# hsa_stm32_board.net
KiCad netlist of a schematic drawn in EAGLE
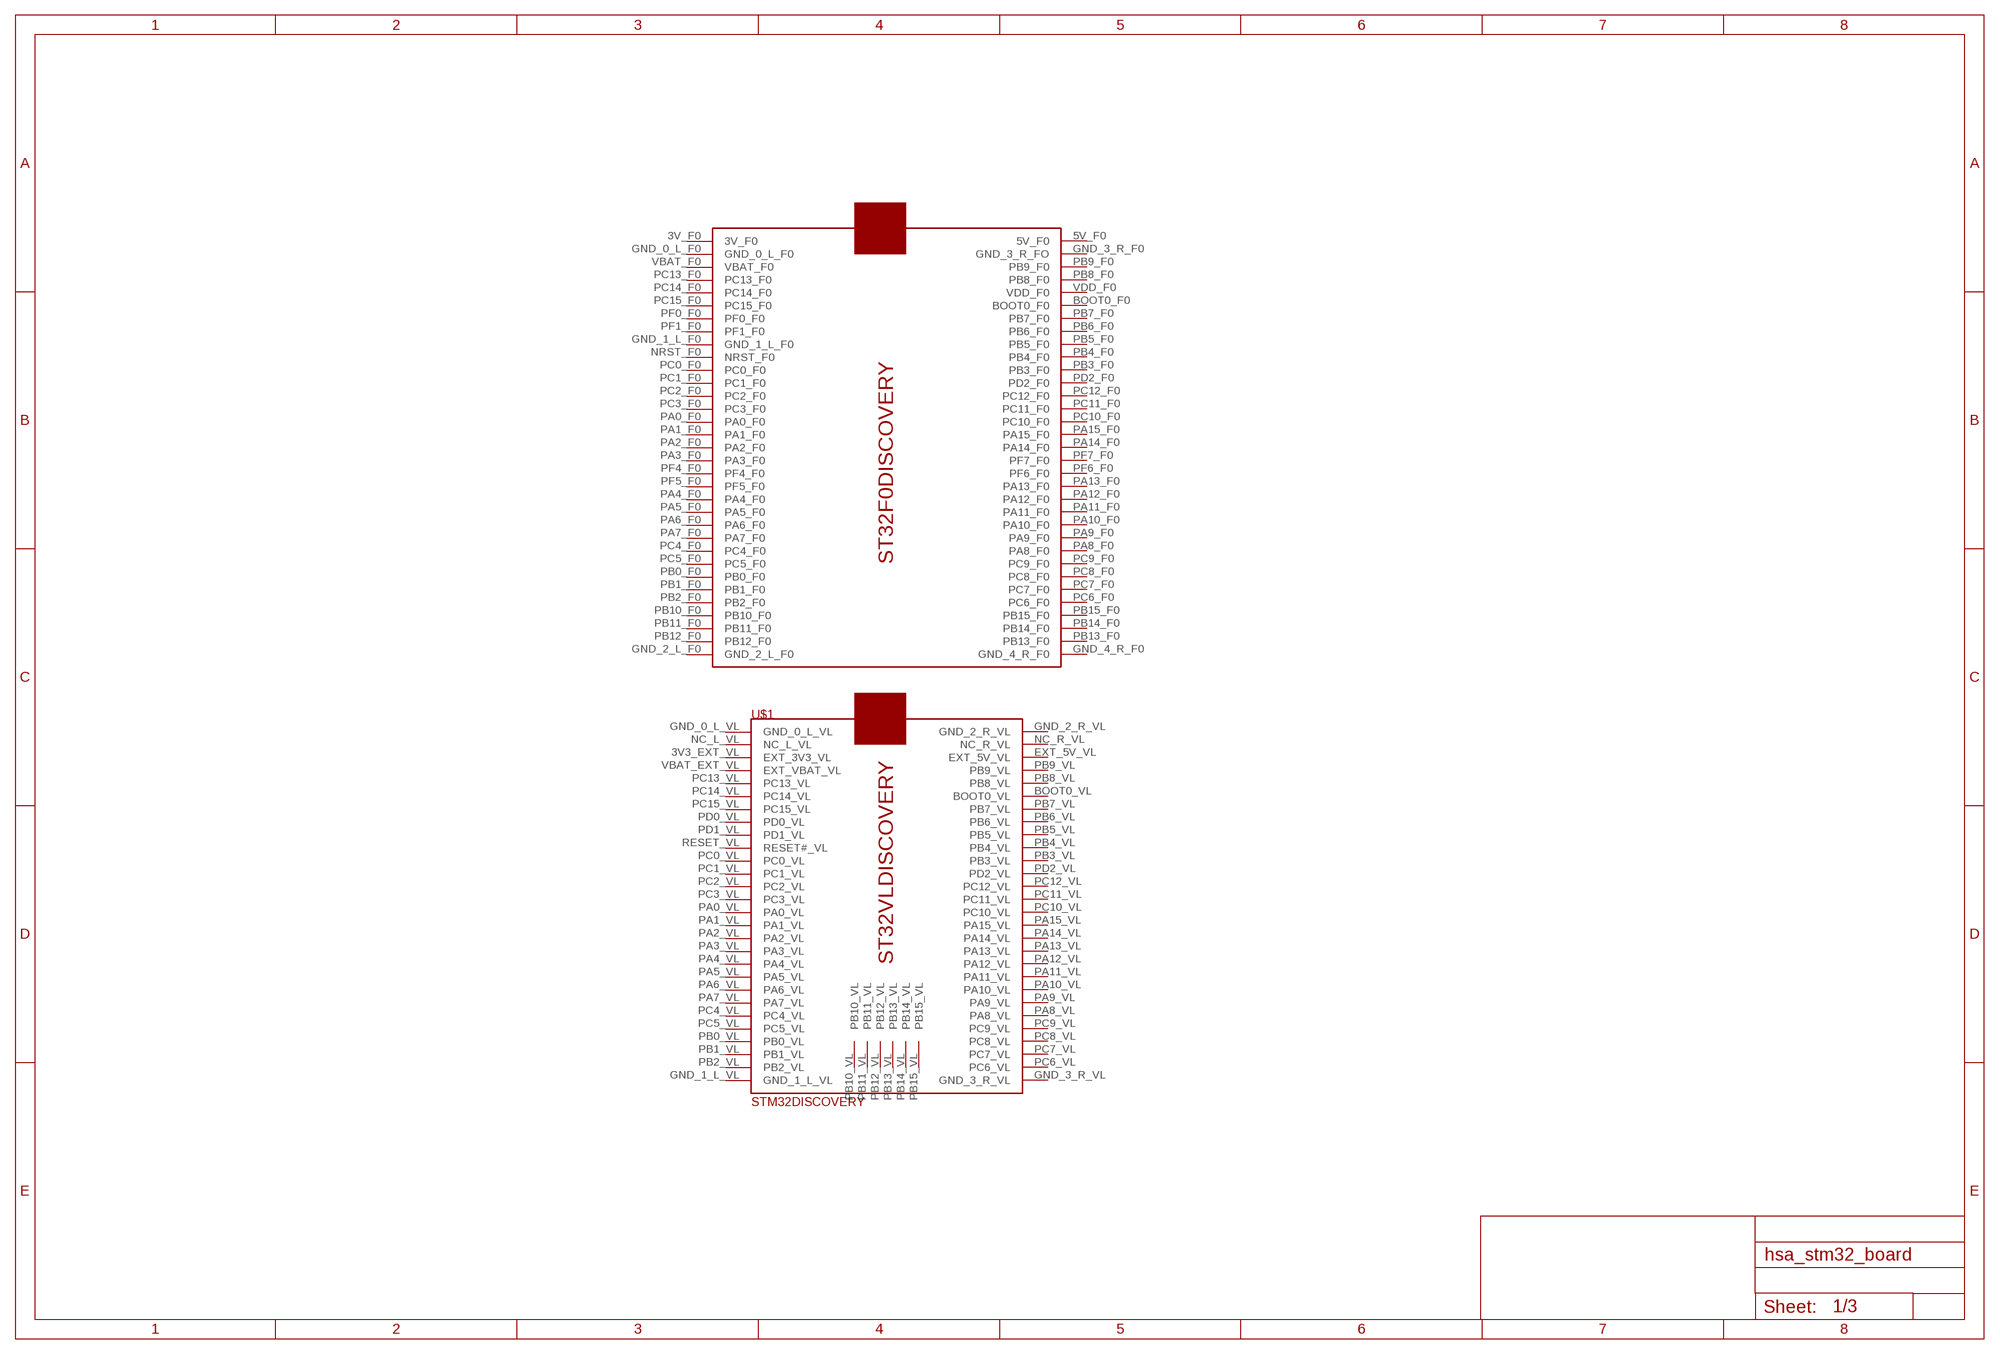
[diagram p0: schematic, sheet 1]
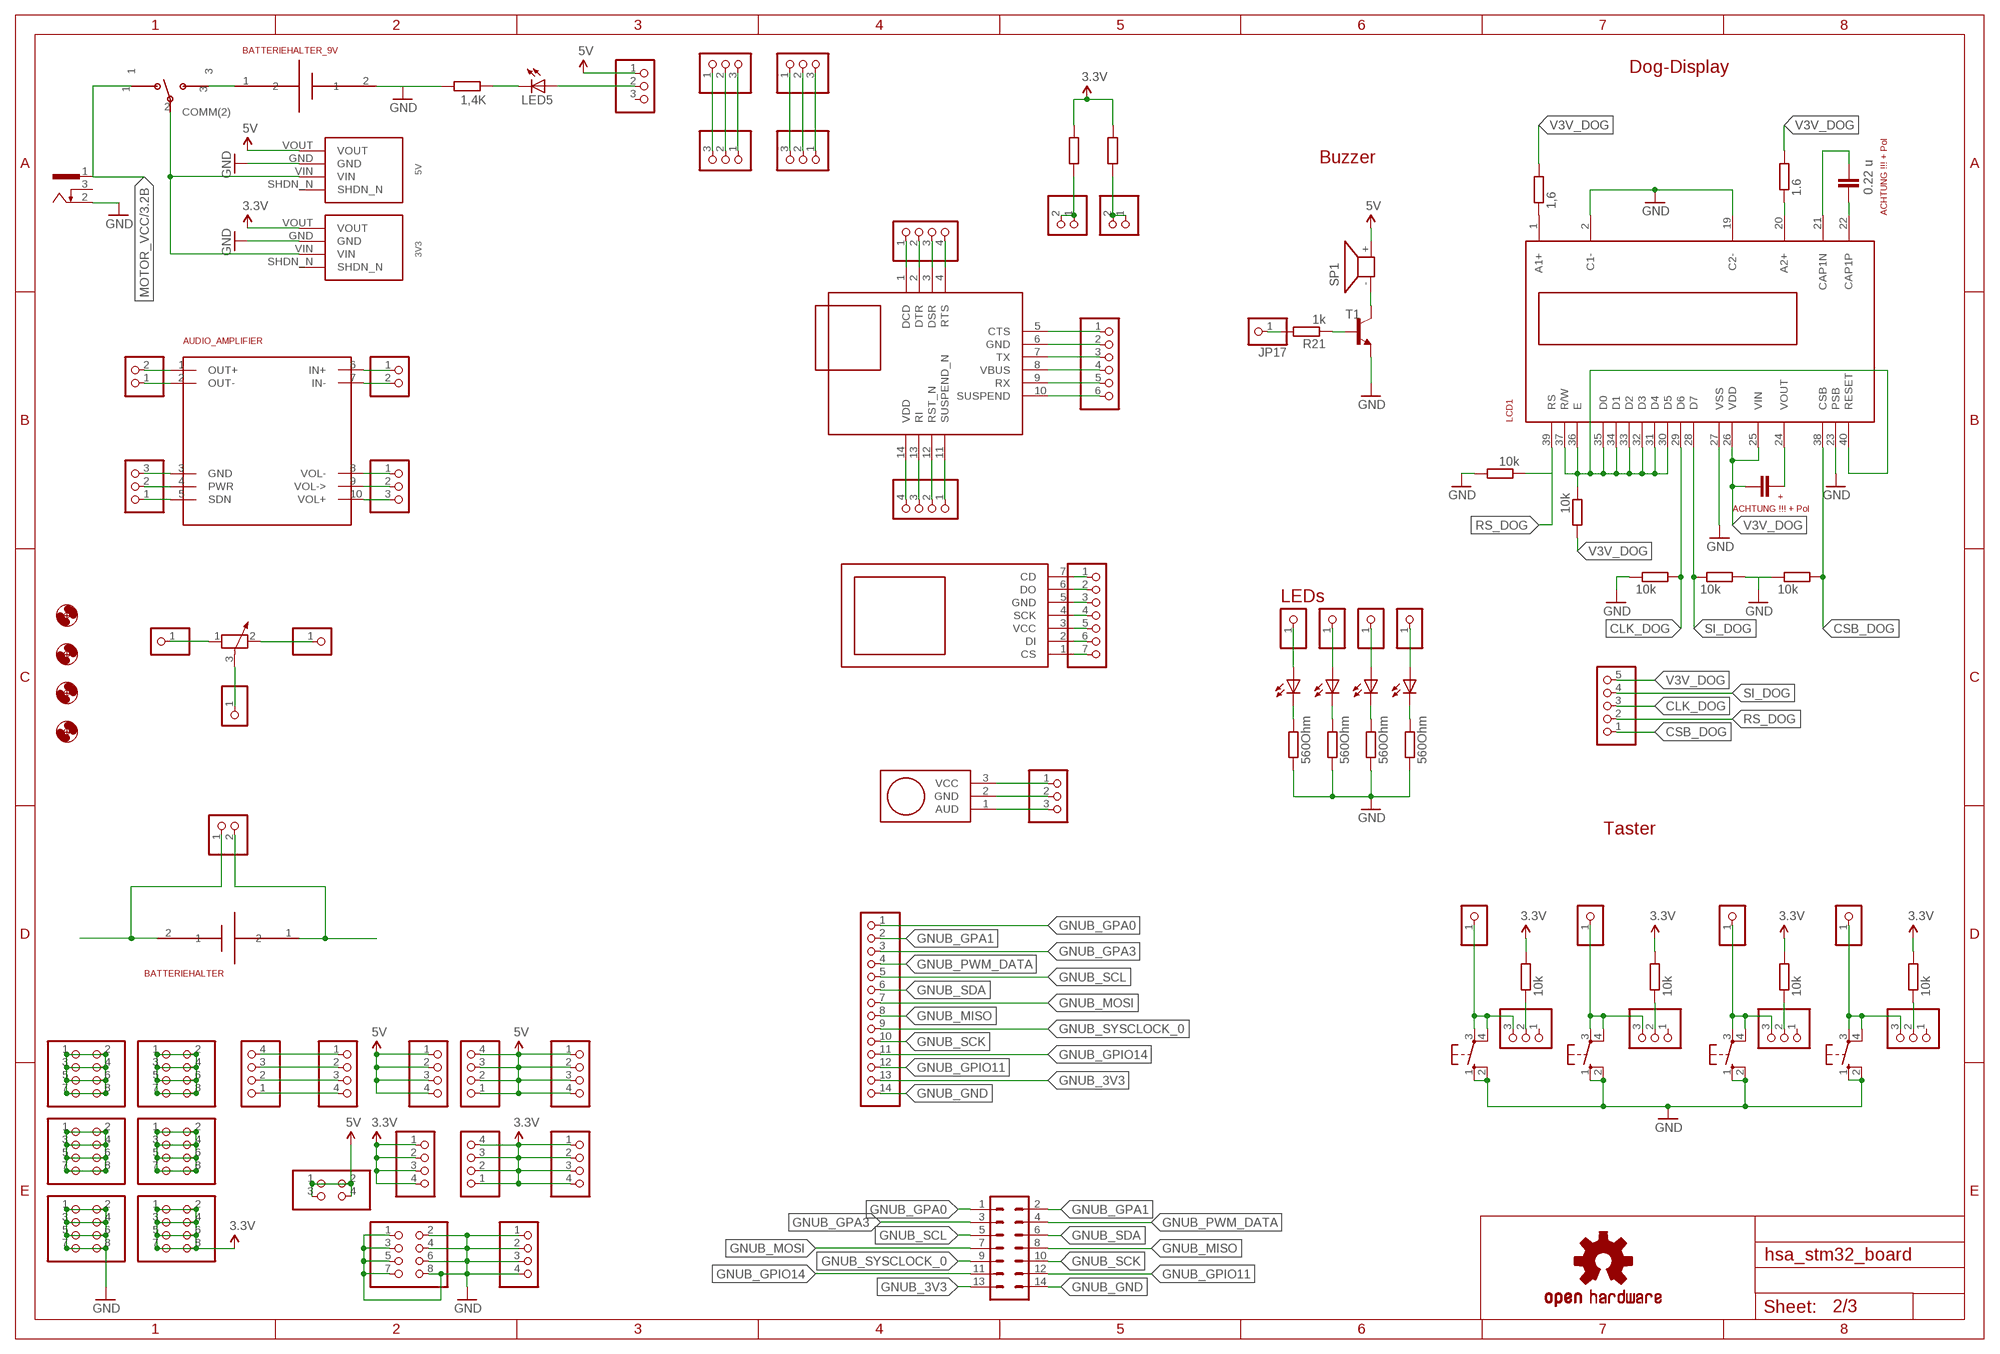
[diagram p1: schematic, sheet 2]
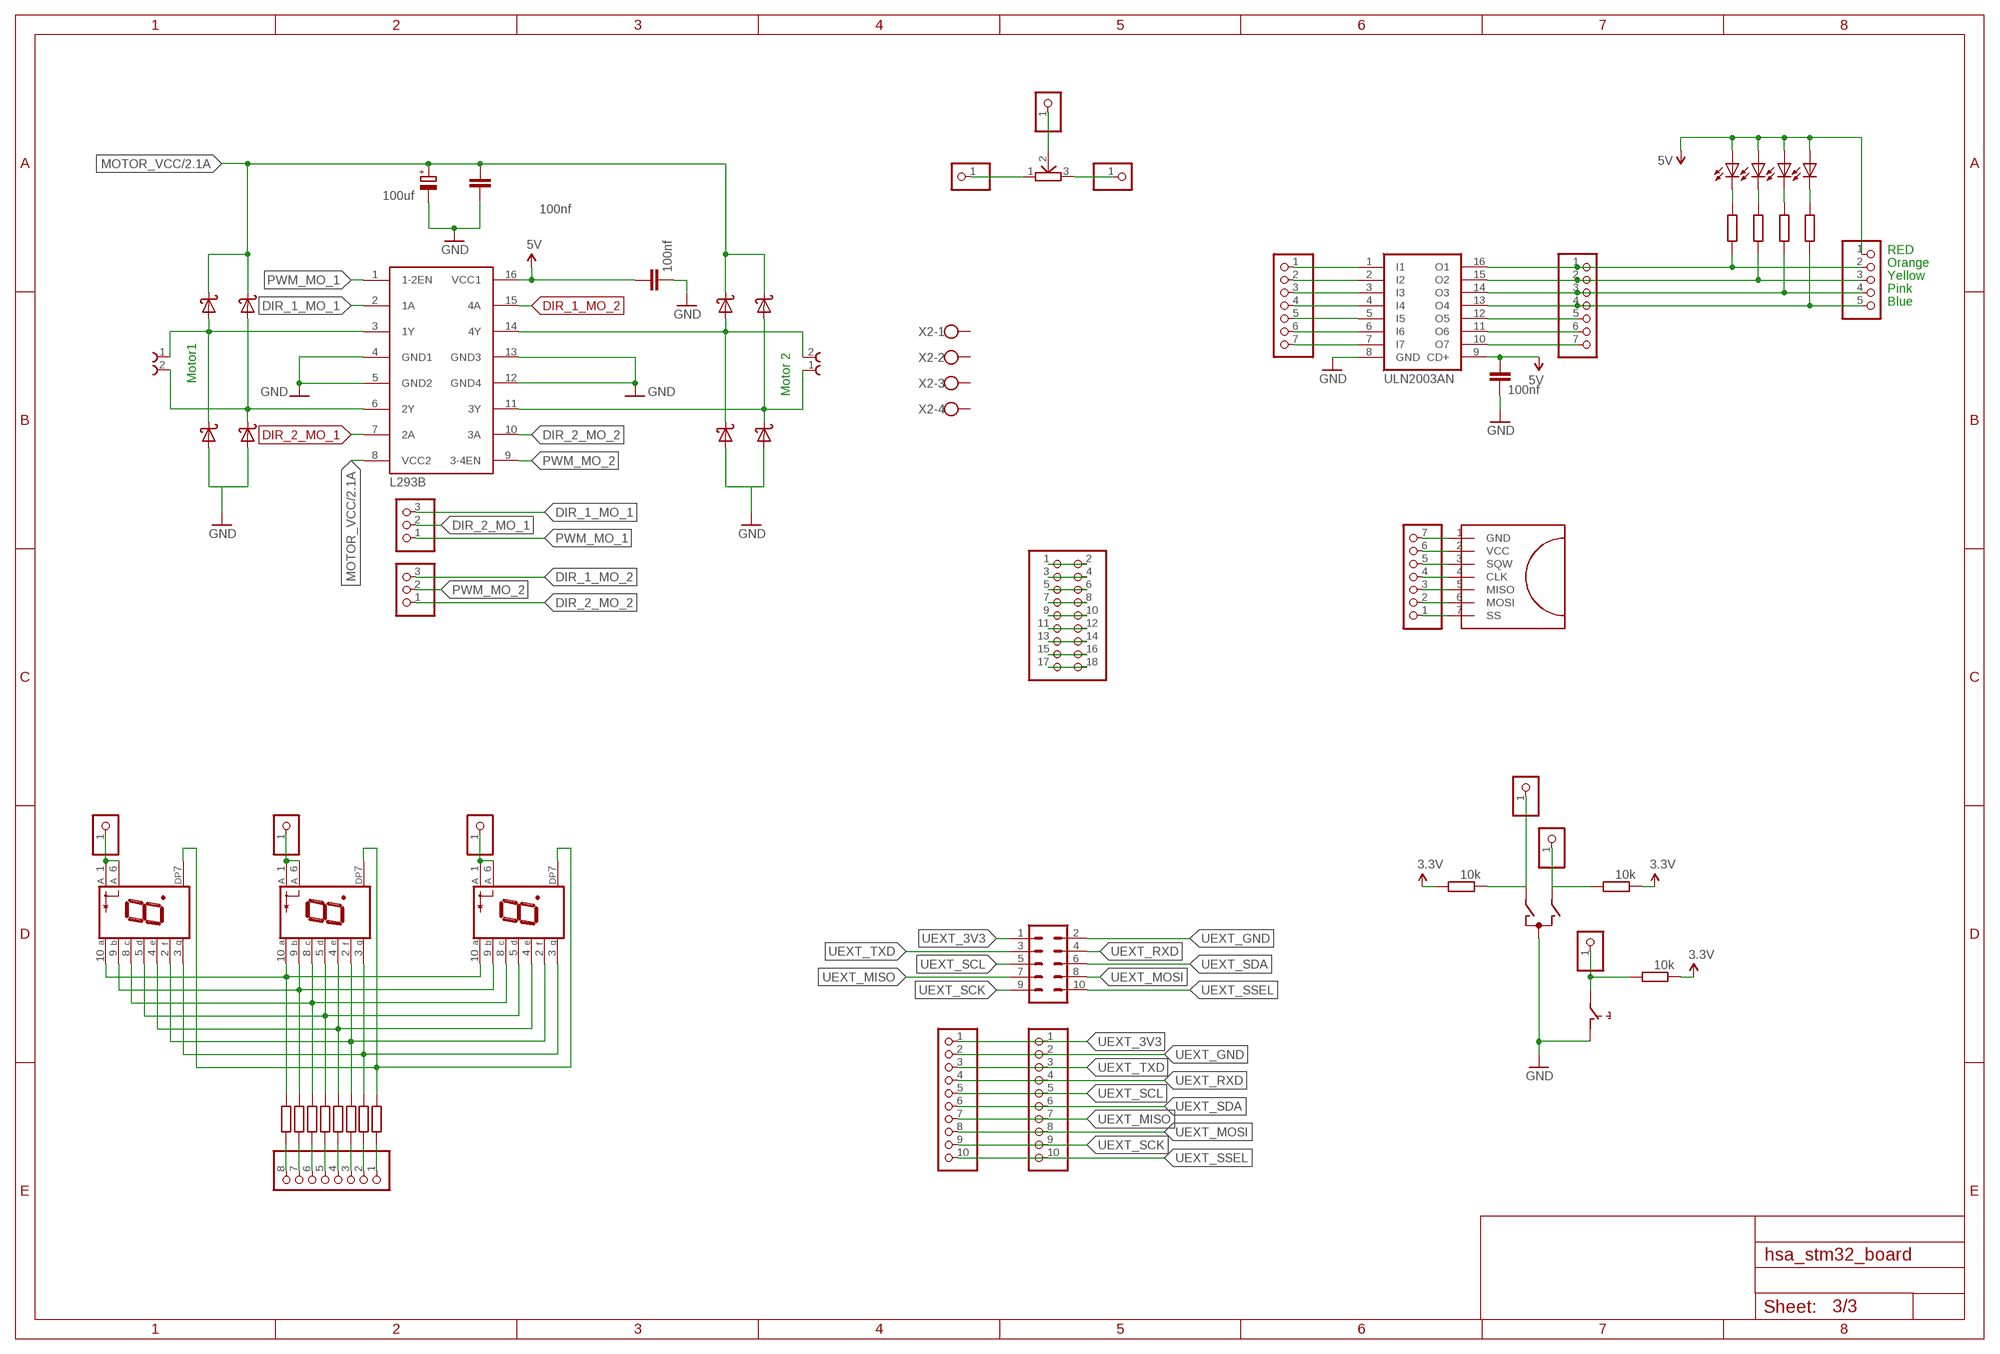
[diagram p2: schematic, sheet 3]

(export (version "E")
  (design (tool "Eeschema 10.0.6"))
  (components
    (comp (ref "C4")
      (value "100nf")
      (footprint "eagle-import:RCL_C025-040X050")
      (libsource (lib "eagle-import") (part "RCL_C-EU025-040X050"))
    )
    (comp (ref "C5")
      (value "100nf")
      (footprint "eagle-import:RCL_C025-040X050")
      (libsource (lib "eagle-import") (part "RCL_C-EU025-040X050"))
    )
    (comp (ref "C6")
      (value "100nf")
      (footprint "eagle-import:RCL_C025-040X050")
      (libsource (lib "eagle-import") (part "RCL_C-EU025-040X050"))
    )
    (comp (ref "C7")
      (value "100uf")
      (footprint "eagle-import:RCL_E2,5-6")
      (libsource (lib "eagle-import") (part "RCL_CPOL-EUE2.5-6"))
    )
    (comp (ref "D1")
      (value "1N5819")
      (footprint "eagle-import:DO41-10")
      (libsource (lib "eagle-import") (part "1N5819"))
    )
    (comp (ref "D2")
      (value "1N5819")
      (footprint "eagle-import:DO41-10")
      (libsource (lib "eagle-import") (part "1N5819"))
    )
    (comp (ref "D3")
      (value "1N5819")
      (footprint "eagle-import:DO41-10")
      (libsource (lib "eagle-import") (part "1N5819"))
    )
    (comp (ref "D4")
      (value "1N5819")
      (footprint "eagle-import:DO41-10")
      (libsource (lib "eagle-import") (part "1N5819"))
    )
    (comp (ref "D5")
      (value "1N5819")
      (footprint "eagle-import:DO41-10")
      (libsource (lib "eagle-import") (part "1N5819"))
    )
    (comp (ref "D6")
      (value "1N5819")
      (footprint "eagle-import:DO41-10")
      (libsource (lib "eagle-import") (part "1N5819"))
    )
    (comp (ref "D7")
      (value "1N5819")
      (footprint "eagle-import:DO41-10")
      (libsource (lib "eagle-import") (part "1N5819"))
    )
    (comp (ref "D8")
      (value "1N5819")
      (footprint "eagle-import:DO41-10")
      (libsource (lib "eagle-import") (part "1N5819"))
    )
    (comp (ref "IC1")
      (value "ULN2003AN")
      (footprint "eagle-import:DIL16")
      (libsource (lib "eagle-import") (part "ULN2003AN"))
    )
    (comp (ref "IC2")
      (value "L293D")
      (footprint "eagle-import:DIL16")
      (libsource (lib "eagle-import") (part "L293D"))
    )
    (comp (ref "JP2")
      (value "PINHD-1X1")
      (footprint "eagle-import:1X01")
      (libsource (lib "eagle-import") (part "PINHD-1X1"))
    )
    (comp (ref "JP3")
      (value "PINHD-1X1")
      (footprint "eagle-import:1X01")
      (libsource (lib "eagle-import") (part "PINHD-1X1"))
    )
    (comp (ref "JP13")
      (value "PINHD-1X1")
      (footprint "eagle-import:1X01")
      (libsource (lib "eagle-import") (part "PINHD-1X1"))
    )
    (comp (ref "JP20")
      (value "PINHD-1X10")
      (footprint "eagle-import:1X10")
      (libsource (lib "eagle-import") (part "PINHD-1X10"))
    )
    (comp (ref "JP21")
      (value "PINHD-1X7")
      (footprint "eagle-import:1X07")
      (libsource (lib "eagle-import") (part "PINHD-1X7"))
    )
    (comp (ref "JP22")
      (value "PINHD-1X8")
      (footprint "eagle-import:1X08")
      (libsource (lib "eagle-import") (part "PINHD-1X8"))
    )
    (comp (ref "JP23")
      (value "PINHD-1X1")
      (footprint "eagle-import:1X01")
      (libsource (lib "eagle-import") (part "PINHD-1X1"))
    )
    (comp (ref "JP25")
      (value "PINHD-1X5/90")
      (footprint "eagle-import:1X05_90")
      (libsource (lib "eagle-import") (part "PINHD-1X5/90"))
    )
    (comp (ref "JP26")
      (value "PINHD-1X7")
      (footprint "eagle-import:1X07")
      (libsource (lib "eagle-import") (part "PINHD-1X7"))
    )
    (comp (ref "JP35")
      (value "PINHD-1X7")
      (footprint "eagle-import:1X07")
      (libsource (lib "eagle-import") (part "PINHD-1X7"))
    )
    (comp (ref "JP53")
      (value "PINHD-1X1")
      (footprint "eagle-import:1X01")
      (libsource (lib "eagle-import") (part "PINHD-1X1"))
    )
    (comp (ref "JP54")
      (value "PINHD-1X1")
      (footprint "eagle-import:1X01")
      (libsource (lib "eagle-import") (part "PINHD-1X1"))
    )
    (comp (ref "JP55")
      (value "PINHD-1X1")
      (footprint "eagle-import:1X01")
      (libsource (lib "eagle-import") (part "PINHD-1X1"))
    )
    (comp (ref "JP56")
      (value "PINHD-2X9")
      (footprint "eagle-import:2X09")
      (libsource (lib "eagle-import") (part "PINHD-2X9"))
    )
    (comp (ref "JP57")
      (value "PINHD-1X3")
      (footprint "eagle-import:1X03")
      (libsource (lib "eagle-import") (part "PINHD-1X3"))
    )
    (comp (ref "JP58")
      (value "PINHD-1X3")
      (footprint "eagle-import:1X03")
      (libsource (lib "eagle-import") (part "PINHD-1X3"))
    )
    (comp (ref "JP63")
      (value "PINHD-1X10")
      (footprint "eagle-import:1X10")
      (libsource (lib "eagle-import") (part "PINHD-1X10"))
    )
    (comp (ref "JP72")
      (value "PINHD-1X1")
      (footprint "eagle-import:1X01")
      (libsource (lib "eagle-import") (part "PINHD-1X1"))
    )
    (comp (ref "JP73")
      (value "PINHD-1X1")
      (footprint "eagle-import:1X01")
      (libsource (lib "eagle-import") (part "PINHD-1X1"))
    )
    (comp (ref "K1")
      (value "691210910002")
      (footprint "eagle-import:691210910002")
      (libsource (lib "eagle-import") (part "691210910002"))
    )
    (comp (ref "K2")
      (value "691210910002")
      (footprint "eagle-import:691210910002")
      (libsource (lib "eagle-import") (part "691210910002"))
    )
    (comp (ref "LED6")
      (value "LA-401MD")
      (footprint "eagle-import:LA-401")
      (libsource (lib "eagle-import") (part "LA-401DM"))
    )
    (comp (ref "LED7")
      (value "LA-401MD")
      (footprint "eagle-import:LA-401")
      (libsource (lib "eagle-import") (part "LA-401DM"))
    )
    (comp (ref "LED8")
      (value "LA-401MD")
      (footprint "eagle-import:LA-401")
      (libsource (lib "eagle-import") (part "LA-401DM"))
    )
    (comp (ref "LED9")
      (value "LED3MM")
      (footprint "eagle-import:LED3MM")
      (libsource (lib "eagle-import") (part "LED3MM"))
    )
    (comp (ref "LED10")
      (value "LED3MM")
      (footprint "eagle-import:LED3MM")
      (libsource (lib "eagle-import") (part "LED3MM"))
    )
    (comp (ref "LED11")
      (value "LED3MM")
      (footprint "eagle-import:LED3MM")
      (libsource (lib "eagle-import") (part "LED3MM"))
    )
    (comp (ref "LED12")
      (value "LED3MM")
      (footprint "eagle-import:LED3MM")
      (libsource (lib "eagle-import") (part "LED3MM"))
    )
    (comp (ref "R18")
      (value "10k")
      (footprint "eagle-import:0207_10")
      (libsource (lib "eagle-import") (part "R-EU_0207/10"))
    )
    (comp (ref "R19")
      (value "10k")
      (footprint "eagle-import:0207_10")
      (libsource (lib "eagle-import") (part "R-EU_0207/10"))
    )
    (comp (ref "R20")
      (value "10k")
      (footprint "eagle-import:0207_10")
      (libsource (lib "eagle-import") (part "R-EU_0207/10"))
    )
    (comp (ref "R24")
      (value "R-EU_0207/10")
      (footprint "eagle-import:0207_10")
      (libsource (lib "eagle-import") (part "R-EU_0207/10"))
    )
    (comp (ref "R25")
      (value "R-EU_0207/10")
      (footprint "eagle-import:0207_10")
      (libsource (lib "eagle-import") (part "R-EU_0207/10"))
    )
    (comp (ref "R26")
      (value "R-EU_0207/10")
      (footprint "eagle-import:0207_10")
      (libsource (lib "eagle-import") (part "R-EU_0207/10"))
    )
    (comp (ref "R27")
      (value "R-EU_0207/10")
      (footprint "eagle-import:0207_10")
      (libsource (lib "eagle-import") (part "R-EU_0207/10"))
    )
    (comp (ref "R28")
      (value "R-EU_0207/10")
      (footprint "eagle-import:0207_10")
      (libsource (lib "eagle-import") (part "R-EU_0207/10"))
    )
    (comp (ref "R29")
      (value "R-EU_0207/10")
      (footprint "eagle-import:0207_10")
      (libsource (lib "eagle-import") (part "R-EU_0207/10"))
    )
    (comp (ref "R30")
      (value "R-EU_0207/10")
      (footprint "eagle-import:0207_10")
      (libsource (lib "eagle-import") (part "R-EU_0207/10"))
    )
    (comp (ref "R31")
      (value "R-EU_0207/10")
      (footprint "eagle-import:0207_10")
      (libsource (lib "eagle-import") (part "R-EU_0207/10"))
    )
    (comp (ref "R32")
      (value "R-EU_0207/10")
      (footprint "eagle-import:0207_10")
      (libsource (lib "eagle-import") (part "R-EU_0207/10"))
    )
    (comp (ref "R33")
      (value "R-EU_0207/10")
      (footprint "eagle-import:0207_10")
      (libsource (lib "eagle-import") (part "R-EU_0207/10"))
    )
    (comp (ref "R34")
      (value "R-EU_0207/10")
      (footprint "eagle-import:0207_10")
      (libsource (lib "eagle-import") (part "R-EU_0207/10"))
    )
    (comp (ref "R35")
      (value "R-EU_0207/10")
      (footprint "eagle-import:0207_10")
      (libsource (lib "eagle-import") (part "R-EU_0207/10"))
    )
    (comp (ref "SV2")
      (value "CON-HARTING-ML_ML10")
      (footprint "eagle-import:CON-HARTING-ML_ML10")
      (libsource (lib "eagle-import") (part "CON-HARTING-ML_ML10"))
    )
    (comp (ref "SW1")
      (value "EC12E_SW")
      (footprint "eagle-import:ALPS_EC12E_SW")
      (fields (field (name "MPN") "EC12E2424407"))
      (libsource (lib "eagle-import") (part "EC12E_SW"))
    )
    (comp (ref "U$10")
      (value "RTC")
      (footprint "eagle-import:RTC")
      (libsource (lib "eagle-import") (part "RTC"))
    )
    (comp (ref "U$17")
      (value "THUMBWHEEL_POTI")
      (footprint "eagle-import:THUMBWHEEL_POTI")
      (libsource (lib "eagle-import") (part "THUMBWHEEL_POTI"))
    )
    (comp (ref "X2")
      (value "W237-4")
      (footprint "eagle-import:W237-4")
      (libsource (lib "eagle-import") (part "W237-4"))
    )
    (comp (ref "U$1")
      (value "STM32DISCOVERY")
      (footprint "eagle-import:STM32DISCOVERY")
      (libsource (lib "eagle-import") (part "STM32DISCOVERY"))
    )
    (comp (ref "3V3")
      (value "VOLTAGE_REGULATOR")
      (footprint "eagle-import:VOL_REG")
      (libsource (lib "eagle-import") (part "VOLTAGE_REGULATOR"))
    )
    (comp (ref "5V")
      (value "VOLTAGE_REGULATOR")
      (footprint "eagle-import:VOL_REG")
      (libsource (lib "eagle-import") (part "VOLTAGE_REGULATOR"))
    )
    (comp (ref "C2")
      (value "0.22 u")
      (footprint "eagle-import:C025-040X050")
      (libsource (lib "eagle-import") (part "C-EU025-040X050"))
    )
    (comp (ref "C3")
      (value "1 u")
      (footprint "eagle-import:C025-040X050")
      (libsource (lib "eagle-import") (part "C-EU025-040X050"))
    )
    (comp (ref "H1")
      (value "MOUNT-HOLE6.0")
      (footprint "eagle-import:6,0")
      (libsource (lib "eagle-import") (part "MOUNT-HOLE6.0"))
    )
    (comp (ref "H2")
      (value "MOUNT-HOLE6.0")
      (footprint "eagle-import:6,0")
      (libsource (lib "eagle-import") (part "MOUNT-HOLE6.0"))
    )
    (comp (ref "H3")
      (value "MOUNT-HOLE6.0")
      (footprint "eagle-import:6,0")
      (libsource (lib "eagle-import") (part "MOUNT-HOLE6.0"))
    )
    (comp (ref "H4")
      (value "MOUNT-HOLE6.0")
      (footprint "eagle-import:6,0")
      (libsource (lib "eagle-import") (part "MOUNT-HOLE6.0"))
    )
    (comp (ref "JP1")
      (value "PINHD-1X5")
      (footprint "eagle-import:1X05")
      (libsource (lib "eagle-import") (part "PINHD-1X5"))
    )
    (comp (ref "JP4")
      (value "PINHD-1X3")
      (footprint "eagle-import:1X03")
      (libsource (lib "eagle-import") (part "PINHD-1X3"))
    )
    (comp (ref "JP5")
      (value "PINHD-1X1")
      (footprint "eagle-import:1X01")
      (libsource (lib "eagle-import") (part "PINHD-1X1"))
    )
    (comp (ref "JP6")
      (value "PINHD-1X1")
      (footprint "eagle-import:1X01")
      (libsource (lib "eagle-import") (part "PINHD-1X1"))
    )
    (comp (ref "JP7")
      (value "PINHD-1X1")
      (footprint "eagle-import:1X01")
      (libsource (lib "eagle-import") (part "PINHD-1X1"))
    )
    (comp (ref "JP8")
      (value "PINHD-1X1")
      (footprint "eagle-import:1X01")
      (libsource (lib "eagle-import") (part "PINHD-1X1"))
    )
    (comp (ref "JP9")
      (value "PINHD-1X1")
      (footprint "eagle-import:1X01")
      (libsource (lib "eagle-import") (part "PINHD-1X1"))
    )
    (comp (ref "JP10")
      (value "PINHD-1X1")
      (footprint "eagle-import:1X01")
      (libsource (lib "eagle-import") (part "PINHD-1X1"))
    )
    (comp (ref "JP11")
      (value "PINHD-1X1")
      (footprint "eagle-import:1X01")
      (libsource (lib "eagle-import") (part "PINHD-1X1"))
    )
    (comp (ref "JP12")
      (value "PINHD-1X1")
      (footprint "eagle-import:1X01")
      (libsource (lib "eagle-import") (part "PINHD-1X1"))
    )
    (comp (ref "JP14")
      (value "PINHD-1X1")
      (footprint "eagle-import:1X01")
      (libsource (lib "eagle-import") (part "PINHD-1X1"))
    )
    (comp (ref "JP15")
      (value "PINHD-1X1")
      (footprint "eagle-import:1X01")
      (libsource (lib "eagle-import") (part "PINHD-1X1"))
    )
    (comp (ref "JP16")
      (value "PINHD-1X1")
      (footprint "eagle-import:1X01")
      (libsource (lib "eagle-import") (part "PINHD-1X1"))
    )
    (comp (ref "JP17")
      (value "PINHD-1X1")
      (footprint "eagle-import:1X01")
      (libsource (lib "eagle-import") (part "PINHD-1X1"))
    )
    (comp (ref "JP18")
      (value "PINHD-2X4")
      (footprint "eagle-import:2X04")
      (libsource (lib "eagle-import") (part "PINHD-2X4"))
    )
    (comp (ref "JP24")
      (value "PINHD-1X4")
      (footprint "eagle-import:1X04")
      (libsource (lib "eagle-import") (part "PINHD-1X4"))
    )
    (comp (ref "JP27")
      (value "PINHD-1X4/90")
      (footprint "eagle-import:1X04_90")
      (libsource (lib "eagle-import") (part "PINHD-1X4/90"))
    )
    (comp (ref "JP28")
      (value "PINHD-1X4")
      (footprint "eagle-import:1X04")
      (libsource (lib "eagle-import") (part "PINHD-1X4"))
    )
    (comp (ref "JP29")
      (value "PINHD-1X4")
      (footprint "eagle-import:1X04")
      (libsource (lib "eagle-import") (part "PINHD-1X4"))
    )
    (comp (ref "JP30")
      (value "PINHD-1X3")
      (footprint "eagle-import:1X03")
      (libsource (lib "eagle-import") (part "PINHD-1X3"))
    )
    (comp (ref "JP31")
      (value "PINHD-1X2")
      (footprint "eagle-import:1X02")
      (libsource (lib "eagle-import") (part "PINHD-1X2"))
    )
    (comp (ref "JP32")
      (value "PINHD-1X2")
      (footprint "eagle-import:1X02")
      (libsource (lib "eagle-import") (part "PINHD-1X2"))
    )
    (comp (ref "JP33")
      (value "PINHD-1X3")
      (footprint "eagle-import:1X03")
      (libsource (lib "eagle-import") (part "PINHD-1X3"))
    )
    (comp (ref "JP34")
      (value "PINHD-1X3")
      (footprint "eagle-import:1X03")
      (libsource (lib "eagle-import") (part "PINHD-1X3"))
    )
    (comp (ref "JP36")
      (value "PINHD-1X4")
      (footprint "eagle-import:1X04")
      (libsource (lib "eagle-import") (part "PINHD-1X4"))
    )
    (comp (ref "JP37")
      (value "PINHD-1X4")
      (footprint "eagle-import:1X04")
      (libsource (lib "eagle-import") (part "PINHD-1X4"))
    )
    (comp (ref "JP38")
      (value "PINHD-1X6")
      (footprint "eagle-import:1X06")
      (libsource (lib "eagle-import") (part "PINHD-1X6"))
    )
    (comp (ref "JP39")
      (value "PINHD-1X7")
      (footprint "eagle-import:1X07")
      (libsource (lib "eagle-import") (part "PINHD-1X7"))
    )
    (comp (ref "JP40")
      (value "PINHD-1X4")
      (footprint "eagle-import:1X04")
      (libsource (lib "eagle-import") (part "PINHD-1X4"))
    )
    (comp (ref "JP41")
      (value "PINHD-1X4")
      (footprint "eagle-import:1X04")
      (libsource (lib "eagle-import") (part "PINHD-1X4"))
    )
    (comp (ref "JP42")
      (value "PINHD-1X4")
      (footprint "eagle-import:1X04")
      (libsource (lib "eagle-import") (part "PINHD-1X4"))
    )
    (comp (ref "JP43")
      (value "PINHD-1X2")
      (footprint "eagle-import:1X02")
      (libsource (lib "eagle-import") (part "PINHD-1X2"))
    )
    (comp (ref "JP44")
      (value "PINHD-2X4")
      (footprint "eagle-import:2X04")
      (libsource (lib "eagle-import") (part "PINHD-2X4"))
    )
    (comp (ref "JP45")
      (value "PINHD-2X4")
      (footprint "eagle-import:2X04")
      (libsource (lib "eagle-import") (part "PINHD-2X4"))
    )
    (comp (ref "JP47")
      (value "PINHD-1X4")
      (footprint "eagle-import:1X04")
      (libsource (lib "eagle-import") (part "PINHD-1X4"))
    )
    (comp (ref "JP48")
      (value "PINHD-1X4")
      (footprint "eagle-import:1X04")
      (libsource (lib "eagle-import") (part "PINHD-1X4"))
    )
    (comp (ref "JP49")
      (value "PINHD-1X3/90")
      (footprint "eagle-import:1X03_90")
      (libsource (lib "eagle-import") (part "PINHD-1X3/90"))
    )
    (comp (ref "JP50")
      (value "PINHD-1X3")
      (footprint "eagle-import:1X03")
      (libsource (lib "eagle-import") (part "PINHD-1X3"))
    )
    (comp (ref "JP51")
      (value "PINHD-1X3/90")
      (footprint "eagle-import:1X03_90")
      (libsource (lib "eagle-import") (part "PINHD-1X3/90"))
    )
    (comp (ref "JP52")
      (value "PINHD-1X3")
      (footprint "eagle-import:1X03")
      (libsource (lib "eagle-import") (part "PINHD-1X3"))
    )
    (comp (ref "JP59")
      (value "PINHD-1X3")
      (footprint "eagle-import:1X03")
      (libsource (lib "eagle-import") (part "PINHD-1X3"))
    )
    (comp (ref "JP60")
      (value "PINHD-1X3")
      (footprint "eagle-import:1X03")
      (libsource (lib "eagle-import") (part "PINHD-1X3"))
    )
    (comp (ref "JP61")
      (value "PINHD-1X3")
      (footprint "eagle-import:1X03")
      (libsource (lib "eagle-import") (part "PINHD-1X3"))
    )
    (comp (ref "JP62")
      (value "PINHD-1X3")
      (footprint "eagle-import:1X03")
      (libsource (lib "eagle-import") (part "PINHD-1X3"))
    )
    (comp (ref "JP64")
      (value "PINHD-1X14")
      (footprint "eagle-import:1X14")
      (libsource (lib "eagle-import") (part "PINHD-1X14"))
    )
    (comp (ref "JP65")
      (value "PINHD-1X2")
      (footprint "eagle-import:1X02")
      (libsource (lib "eagle-import") (part "PINHD-1X2"))
    )
    (comp (ref "JP66")
      (value "PINHD-1X2")
      (footprint "eagle-import:1X02")
      (libsource (lib "eagle-import") (part "PINHD-1X2"))
    )
    (comp (ref "JP67")
      (value "PINHD-2X4")
      (footprint "eagle-import:2X04")
      (libsource (lib "eagle-import") (part "PINHD-2X4"))
    )
    (comp (ref "JP68")
      (value "PINHD-2X4")
      (footprint "eagle-import:2X04")
      (libsource (lib "eagle-import") (part "PINHD-2X4"))
    )
    (comp (ref "JP69")
      (value "PINHD-2X4")
      (footprint "eagle-import:2X04")
      (libsource (lib "eagle-import") (part "PINHD-2X4"))
    )
    (comp (ref "JP70")
      (value "PINHD-2X4")
      (footprint "eagle-import:2X04")
      (libsource (lib "eagle-import") (part "PINHD-2X4"))
    )
    (comp (ref "JP71")
      (value "PINHD-2X2")
      (footprint "eagle-import:2X02")
      (libsource (lib "eagle-import") (part "PINHD-2X2"))
    )
    (comp (ref "LCD1")
      (value "ZEITERFASSUNG_-OPTO_DOGM")
      (footprint "eagle-import:ZEITERFASSUNG_-OPTO_DOGM")
      (libsource (lib "eagle-import") (part "ZEITERFASSUNG_-OPTO_DOGM"))
    )
    (comp (ref "LED1")
      (value "LED5MM")
      (footprint "eagle-import:LED5MM")
      (libsource (lib "eagle-import") (part "LED5MM"))
    )
    (comp (ref "LED2")
      (value "LED5MM")
      (footprint "eagle-import:LED5MM")
      (libsource (lib "eagle-import") (part "LED5MM"))
    )
    (comp (ref "LED3")
      (value "LED5MM")
      (footprint "eagle-import:LED5MM")
      (libsource (lib "eagle-import") (part "LED5MM"))
    )
    (comp (ref "LED4")
      (value "LED5MM")
      (footprint "eagle-import:LED5MM")
      (libsource (lib "eagle-import") (part "LED5MM"))
    )
    (comp (ref "LED5")
      (value "LED5MM")
      (footprint "eagle-import:LED5MM")
      (libsource (lib "eagle-import") (part "LED5MM"))
    )
    (comp (ref "LOGO1")
      (value "OSHW-LOGOL")
      (footprint "eagle-import:OSHW-LOGO-L")
      (libsource (lib "eagle-import") (part "OSHW-LOGOL"))
    )
    (comp (ref "R1")
      (value "560Ohm")
      (footprint "eagle-import:0207_10")
      (libsource (lib "eagle-import") (part "R-EU_0207/10"))
    )
    (comp (ref "R2")
      (value "560Ohm")
      (footprint "eagle-import:0207_10")
      (libsource (lib "eagle-import") (part "R-EU_0207/10"))
    )
    (comp (ref "R3")
      (value "560Ohm")
      (footprint "eagle-import:0207_10")
      (libsource (lib "eagle-import") (part "R-EU_0207/10"))
    )
    (comp (ref "R4")
      (value "560Ohm")
      (footprint "eagle-import:0207_10")
      (libsource (lib "eagle-import") (part "R-EU_0207/10"))
    )
    (comp (ref "R5")
      (value "RCL_POTENTIOMETER_PT-10")
      (footprint "eagle-import:RCL_PT-10")
      (libsource (lib "eagle-import") (part "RCL_POTENTIOMETER_PT-10"))
    )
    (comp (ref "R6")
      (value "1,4K")
      (footprint "eagle-import:0207_10")
      (libsource (lib "eagle-import") (part "R-EU_0207/10"))
    )
    (comp (ref "R7")
      (value "1.6")
      (footprint "eagle-import:0207_10")
      (libsource (lib "eagle-import") (part "R-EU_0207/10"))
    )
    (comp (ref "R8")
      (value "1,6")
      (footprint "eagle-import:0207_10")
      (libsource (lib "eagle-import") (part "R-EU_0207/10"))
    )
    (comp (ref "R9")
      (value "10k")
      (footprint "eagle-import:0207_10")
      (libsource (lib "eagle-import") (part "R-EU_0207/10"))
    )
    (comp (ref "R10")
      (value "10k")
      (footprint "eagle-import:0207_10")
      (libsource (lib "eagle-import") (part "R-EU_0207/10"))
    )
    (comp (ref "R11")
      (value "10k")
      (footprint "eagle-import:0207_10")
      (libsource (lib "eagle-import") (part "R-EU_0207/10"))
    )
    (comp (ref "R12")
      (value "10k")
      (footprint "eagle-import:0207_10")
      (libsource (lib "eagle-import") (part "R-EU_0207/10"))
    )
    (comp (ref "R13")
      (value "10k")
      (footprint "eagle-import:0207_10")
      (libsource (lib "eagle-import") (part "R-EU_0207/10"))
    )
    (comp (ref "R14")
      (value "10k")
      (footprint "eagle-import:0207_10")
      (libsource (lib "eagle-import") (part "R-EU_0207/10"))
    )
    (comp (ref "R15")
      (value "10k")
      (footprint "eagle-import:0207_10")
      (libsource (lib "eagle-import") (part "R-EU_0207/10"))
    )
    (comp (ref "R16")
      (value "10k")
      (footprint "eagle-import:0207_10")
      (libsource (lib "eagle-import") (part "R-EU_0207/10"))
    )
    (comp (ref "R17")
      (value "10k")
      (footprint "eagle-import:0207_10")
      (libsource (lib "eagle-import") (part "R-EU_0207/10"))
    )
    (comp (ref "R21")
      (value "1k")
      (footprint "eagle-import:0207_10")
      (libsource (lib "eagle-import") (part "R-EU_0207/10"))
    )
    (comp (ref "R22")
      (value "R-EU_0207/10")
      (footprint "eagle-import:0207_10")
      (libsource (lib "eagle-import") (part "R-EU_0207/10"))
    )
    (comp (ref "R23")
      (value "R-EU_0207/10")
      (footprint "eagle-import:0207_10")
      (libsource (lib "eagle-import") (part "R-EU_0207/10"))
    )
    (comp (ref "S1")
      (value "CPU-K_MODULE_REV3.0_SWITCH-OMRON_10-XX")
      (footprint "eagle-import:CPU-K_MODULE_REV3.0_SWITCH-OMRON_B3F-10XX")
      (libsource (lib "eagle-import") (part "CPU-K_MODULE_REV3.0_SWITCH-OMRON_10-XX"))
    )
    (comp (ref "S2")
      (value "CPU-K_MODULE_REV3.0_SWITCH-OMRON_10-XX")
      (footprint "eagle-import:CPU-K_MODULE_REV3.0_SWITCH-OMRON_B3F-10XX")
      (libsource (lib "eagle-import") (part "CPU-K_MODULE_REV3.0_SWITCH-OMRON_10-XX"))
    )
    (comp (ref "S3")
      (value "CPU-K_MODULE_REV3.0_SWITCH-OMRON_10-XX")
      (footprint "eagle-import:CPU-K_MODULE_REV3.0_SWITCH-OMRON_B3F-10XX")
      (libsource (lib "eagle-import") (part "CPU-K_MODULE_REV3.0_SWITCH-OMRON_10-XX"))
    )
    (comp (ref "S4")
      (value "CPU-K_MODULE_REV3.0_SWITCH-OMRON_10-XX")
      (footprint "eagle-import:CPU-K_MODULE_REV3.0_SWITCH-OMRON_B3F-10XX")
      (libsource (lib "eagle-import") (part "CPU-K_MODULE_REV3.0_SWITCH-OMRON_10-XX"))
    )
    (comp (ref "SP1")
      (value "BUZZER_F/PMX04")
      (footprint "eagle-import:BUZZER_F_PMX04A")
      (libsource (lib "eagle-import") (part "BUZZER_F/PMX04"))
    )
    (comp (ref "SV3")
      (value "ML14")
      (footprint "eagle-import:ML14")
      (libsource (lib "eagle-import") (part "ML14"))
    )
    (comp (ref "T1")
      (value "TRANSISTOR_BC337")
      (footprint "eagle-import:TRANSISTOR_TO92")
      (libsource (lib "eagle-import") (part "TRANSISTOR_BC337"))
    )
    (comp (ref "U$2")
      (value "USB_TO_SERIAL_ADAPTER")
      (footprint "eagle-import:USB_TO_SERIAL")
      (libsource (lib "eagle-import") (part "USB_TO_SERIAL_ADAPTER"))
    )
    (comp (ref "U$4")
      (value "KIPPSCHALTER(EIN,AUS,EIN)")
      (footprint "eagle-import:KIPPSCHALTER")
      (libsource (lib "eagle-import") (part "KIPPSCHALTER(EIN,AUS,EIN)"))
    )
    (comp (ref "U$5")
      (value "MIC")
      (footprint "eagle-import:MIC")
      (libsource (lib "eagle-import") (part "MIC"))
    )
    (comp (ref "U$6")
      (value "BATTERIEHALTER")
      (footprint "eagle-import:BH_KZH_20")
      (libsource (lib "eagle-import") (part "BATTERIEHALTER"))
    )
    (comp (ref "U$7")
      (value "BATTERIEHALTER_9V")
      (footprint "eagle-import:BATTERIEHALTER_9V")
      (libsource (lib "eagle-import") (part "BATTERIEHALTER_9V"))
    )
    (comp (ref "U$9")
      (value "AUDIO_AMPLIFIER")
      (footprint "eagle-import:AUDIO_AMPLIFIER")
      (libsource (lib "eagle-import") (part "AUDIO_AMPLIFIER"))
    )
    (comp (ref "U$12")
      (value "MICRO_SD_HALTER")
      (footprint "eagle-import:MIKRO_SD_HALTER")
      (libsource (lib "eagle-import") (part "MICRO_SD_HALTER"))
    )
    (comp (ref "X1")
      (value "733980-62")
      (footprint "eagle-import:733980-62")
      (libsource (lib "eagle-import") (part "73398?0-62"))
    )
  )
  (nets
    (net (code "1") (name "3.3V") (class "Default")
      (node (ref "3V3") (pin "VOUT") (pinfunction "VOUT_VOUT") (pintype "bidirectional"))
      (node (ref "JP29") (pin "1") (pinfunction "1_1") (pintype "passive"))
      (node (ref "JP29") (pin "2") (pinfunction "2_2") (pintype "passive"))
      (node (ref "JP29") (pin "3") (pinfunction "3_3") (pintype "passive"))
      (node (ref "JP29") (pin "4") (pinfunction "4_4") (pintype "passive"))
      (node (ref "JP41") (pin "1") (pinfunction "1_1") (pintype "passive"))
      (node (ref "JP41") (pin "2") (pinfunction "2_2") (pintype "passive"))
      (node (ref "JP41") (pin "3") (pinfunction "3_3") (pintype "passive"))
      (node (ref "JP41") (pin "4") (pinfunction "4_4") (pintype "passive"))
      (node (ref "JP47") (pin "1") (pinfunction "1_1") (pintype "passive"))
      (node (ref "JP47") (pin "2") (pinfunction "2_2") (pintype "passive"))
      (node (ref "JP47") (pin "3") (pinfunction "3_3") (pintype "passive"))
      (node (ref "JP47") (pin "4") (pinfunction "4_4") (pintype "passive"))
      (node (ref "JP70") (pin "1") (pinfunction "1_1") (pintype "passive"))
      (node (ref "JP70") (pin "2") (pinfunction "2_2") (pintype "passive"))
      (node (ref "JP70") (pin "3") (pinfunction "3_3") (pintype "passive"))
      (node (ref "JP70") (pin "4") (pinfunction "4_4") (pintype "passive"))
      (node (ref "JP70") (pin "5") (pinfunction "5_5") (pintype "passive"))
      (node (ref "JP70") (pin "6") (pinfunction "6_6") (pintype "passive"))
      (node (ref "JP70") (pin "7") (pinfunction "7_7") (pintype "passive"))
      (node (ref "JP70") (pin "8") (pinfunction "8_8") (pintype "passive"))
      (node (ref "R14") (pin "2") (pinfunction "2_2") (pintype "passive"))
      (node (ref "R15") (pin "2") (pinfunction "2_2") (pintype "passive"))
      (node (ref "R16") (pin "2") (pinfunction "2_2") (pintype "passive"))
      (node (ref "R17") (pin "2") (pinfunction "2_2") (pintype "passive"))
      (node (ref "R18") (pin "1") (pinfunction "1_1") (pintype "passive"))
      (node (ref "R19") (pin "2") (pinfunction "2_2") (pintype "passive"))
      (node (ref "R20") (pin "1") (pinfunction "1_1") (pintype "passive"))
      (node (ref "R22") (pin "2") (pinfunction "2_2") (pintype "passive"))
      (node (ref "R23") (pin "2") (pinfunction "2_2") (pintype "passive"))
    )
    (net (code "2") (name "5V") (class "Default")
      (node (ref "5V") (pin "VOUT") (pinfunction "VOUT_VOUT") (pintype "bidirectional"))
      (node (ref "C4") (pin "1") (pinfunction "1_1") (pintype "passive"))
      (node (ref "C6") (pin "1") (pinfunction "1_1") (pintype "passive"))
      (node (ref "IC1") (pin "9") (pinfunction "CD+_9") (pintype "passive"))
      (node (ref "IC2") (pin "16") (pinfunction "VCC1_16") (pintype "power_in"))
      (node (ref "JP25") (pin "1") (pinfunction "1_1") (pintype "passive"))
      (node (ref "JP28") (pin "1") (pinfunction "1_1") (pintype "passive"))
      (node (ref "JP28") (pin "2") (pinfunction "2_2") (pintype "passive"))
      (node (ref "JP28") (pin "3") (pinfunction "3_3") (pintype "passive"))
      (node (ref "JP28") (pin "4") (pinfunction "4_4") (pintype "passive"))
      (node (ref "JP4") (pin "1") (pinfunction "1_1") (pintype "passive"))
      (node (ref "JP40") (pin "1") (pinfunction "1_1") (pintype "passive"))
      (node (ref "JP40") (pin "2") (pinfunction "2_2") (pintype "passive"))
      (node (ref "JP40") (pin "3") (pinfunction "3_3") (pintype "passive"))
      (node (ref "JP40") (pin "4") (pinfunction "4_4") (pintype "passive"))
      (node (ref "JP48") (pin "1") (pinfunction "1_1") (pintype "passive"))
      (node (ref "JP48") (pin "2") (pinfunction "2_2") (pintype "passive"))
      (node (ref "JP48") (pin "3") (pinfunction "3_3") (pintype "passive"))
      (node (ref "JP48") (pin "4") (pinfunction "4_4") (pintype "passive"))
      (node (ref "JP71") (pin "1") (pinfunction "1_1") (pintype "passive"))
      (node (ref "JP71") (pin "2") (pinfunction "2_2") (pintype "passive"))
      (node (ref "JP71") (pin "3") (pinfunction "3_3") (pintype "passive"))
      (node (ref "JP71") (pin "4") (pinfunction "4_4") (pintype "passive"))
      (node (ref "LED10") (pin "A") (pinfunction "A_A") (pintype "passive"))
      (node (ref "LED11") (pin "A") (pinfunction "A_A") (pintype "passive"))
      (node (ref "LED12") (pin "A") (pinfunction "A_A") (pintype "passive"))
      (node (ref "LED9") (pin "A") (pinfunction "A_A") (pintype "passive"))
      (node (ref "SP1") (pin "+") (pinfunction "2_+") (pintype "passive"))
    )
    (net (code "3") (name "CLK_DOG") (class "Default")
      (node (ref "JP1") (pin "3") (pinfunction "3_3") (pintype "passive"))
      (node (ref "LCD1") (pin "29") (pinfunction "D6_29") (pintype "bidirectional"))
      (node (ref "R11") (pin "2") (pinfunction "2_2") (pintype "passive"))
    )
    (net (code "4") (name "CSB_DOG") (class "Default")
      (node (ref "JP1") (pin "1") (pinfunction "1_1") (pintype "passive"))
      (node (ref "LCD1") (pin "38") (pinfunction "CSB_38") (pintype "bidirectional"))
      (node (ref "R13") (pin "2") (pinfunction "2_2") (pintype "passive"))
    )
    (net (code "5") (name "DIR_1_MO_1") (class "Default")
      (node (ref "IC2") (pin "2") (pinfunction "1A_2") (pintype "input"))
      (node (ref "JP57") (pin "3") (pinfunction "3_3") (pintype "passive"))
    )
    (net (code "6") (name "DIR_1_MO_2") (class "Default")
      (node (ref "IC2") (pin "15") (pinfunction "4A_15") (pintype "input"))
      (node (ref "JP58") (pin "3") (pinfunction "3_3") (pintype "passive"))
    )
    (net (code "7") (name "DIR_2_MO_1") (class "Default")
      (node (ref "IC2") (pin "7") (pinfunction "2A_7") (pintype "input"))
      (node (ref "JP57") (pin "2") (pinfunction "2_2") (pintype "passive"))
    )
    (net (code "8") (name "DIR_2_MO_2") (class "Default")
      (node (ref "IC2") (pin "10") (pinfunction "3A_10") (pintype "input"))
      (node (ref "JP58") (pin "1") (pinfunction "1_1") (pintype "passive"))
    )
    (net (code "9") (name "GND") (class "Default")
      (node (ref "3V3") (pin "GND") (pinfunction "GND_GND") (pintype "bidirectional"))
      (node (ref "5V") (pin "GND") (pinfunction "GND_GND") (pintype "bidirectional"))
      (node (ref "C4") (pin "2") (pinfunction "2_2") (pintype "passive"))
      (node (ref "C5") (pin "2") (pinfunction "2_2") (pintype "passive"))
      (node (ref "C6") (pin "2") (pinfunction "2_2") (pintype "passive"))
      (node (ref "C7") (pin "-") (pinfunction "-_-") (pintype "passive"))
      (node (ref "D3") (pin "A") (pinfunction "A_A") (pintype "passive"))
      (node (ref "D4") (pin "A") (pinfunction "A_A") (pintype "passive"))
      (node (ref "D7") (pin "A") (pinfunction "A_A") (pintype "passive"))
      (node (ref "D8") (pin "A") (pinfunction "A_A") (pintype "passive"))
      (node (ref "IC1") (pin "8") (pinfunction "GND_8") (pintype "power_in"))
      (node (ref "IC2") (pin "12") (pinfunction "GND4_12") (pintype "power_in"))
      (node (ref "IC2") (pin "13") (pinfunction "GND3_13") (pintype "power_in"))
      (node (ref "IC2") (pin "4") (pinfunction "GND1_4") (pintype "power_in"))
      (node (ref "IC2") (pin "5") (pinfunction "GND2_5") (pintype "power_in"))
      (node (ref "JP18") (pin "1") (pinfunction "1_1") (pintype "passive"))
      (node (ref "JP18") (pin "2") (pinfunction "2_2") (pintype "passive"))
      (node (ref "JP18") (pin "3") (pinfunction "3_3") (pintype "passive"))
      (node (ref "JP18") (pin "4") (pinfunction "4_4") (pintype "passive"))
      (node (ref "JP18") (pin "5") (pinfunction "5_5") (pintype "passive"))
      (node (ref "JP18") (pin "6") (pinfunction "6_6") (pintype "passive"))
      (node (ref "JP18") (pin "7") (pinfunction "7_7") (pintype "passive"))
      (node (ref "JP18") (pin "8") (pinfunction "8_8") (pintype "passive"))
      (node (ref "JP42") (pin "1") (pinfunction "1_1") (pintype "passive"))
      (node (ref "JP42") (pin "2") (pinfunction "2_2") (pintype "passive"))
      (node (ref "JP42") (pin "3") (pinfunction "3_3") (pintype "passive"))
      (node (ref "JP42") (pin "4") (pinfunction "4_4") (pintype "passive"))
      (node (ref "JP67") (pin "1") (pinfunction "1_1") (pintype "passive"))
      (node (ref "JP67") (pin "2") (pinfunction "2_2") (pintype "passive"))
      (node (ref "JP67") (pin "3") (pinfunction "3_3") (pintype "passive"))
      (node (ref "JP67") (pin "4") (pinfunction "4_4") (pintype "passive"))
      (node (ref "JP67") (pin "5") (pinfunction "5_5") (pintype "passive"))
      (node (ref "JP67") (pin "6") (pinfunction "6_6") (pintype "passive"))
      (node (ref "JP67") (pin "7") (pinfunction "7_7") (pintype "passive"))
      (node (ref "JP67") (pin "8") (pinfunction "8_8") (pintype "passive"))
      (node (ref "LCD1") (pin "19") (pinfunction "C2-_19") (pintype "bidirectional"))
      (node (ref "LCD1") (pin "2") (pinfunction "C1-_2") (pintype "bidirectional"))
      (node (ref "LCD1") (pin "23") (pinfunction "PSB_23") (pintype "bidirectional"))
      (node (ref "LCD1") (pin "27") (pinfunction "VSS_27") (pintype "bidirectional"))
      (node (ref "R1") (pin "1") (pinfunction "1_1") (pintype "passive"))
      (node (ref "R11") (pin "1") (pinfunction "1_1") (pintype "passive"))
      (node (ref "R12") (pin "2") (pinfunction "2_2") (pintype "passive"))
      (node (ref "R13") (pin "1") (pinfunction "1_1") (pintype "passive"))
      (node (ref "R2") (pin "1") (pinfunction "1_1") (pintype "passive"))
      (node (ref "R3") (pin "1") (pinfunction "1_1") (pintype "passive"))
      (node (ref "R4") (pin "1") (pinfunction "1_1") (pintype "passive"))
      (node (ref "R6") (pin "2") (pinfunction "2_2") (pintype "passive"))
      (node (ref "R9") (pin "2") (pinfunction "2_2") (pintype "passive"))
      (node (ref "S1") (pin "1") (pinfunction "S_1") (pintype "passive"))
      (node (ref "S1") (pin "2") (pinfunction "S1_2") (pintype "passive"))
      (node (ref "S2") (pin "1") (pinfunction "S_1") (pintype "passive"))
      (node (ref "S2") (pin "2") (pinfunction "S1_2") (pintype "passive"))
      (node (ref "S3") (pin "1") (pinfunction "S_1") (pintype "passive"))
      (node (ref "S3") (pin "2") (pinfunction "S1_2") (pintype "passive"))
      (node (ref "S4") (pin "1") (pinfunction "S_1") (pintype "passive"))
      (node (ref "S4") (pin "2") (pinfunction "S1_2") (pintype "passive"))
      (node (ref "SW1") (pin "C") (pinfunction "C_C") (pintype "passive"))
      (node (ref "SW1") (pin "D") (pinfunction "1_D") (pintype "passive"))
      (node (ref "T1") (pin "1") (pinfunction "E_1") (pintype "passive"))
      (node (ref "U$7") (pin "2") (pinfunction "1_2") (pintype "bidirectional"))
      (node (ref "X1") (pin "2") (pinfunction "2_2") (pintype "passive"))
    )
    (net (code "10") (name "GND_1_L_VL") (class "Default")
      (node (ref "U$1") (pin "GND_1_L_VL") (pinfunction "GND_1_L_VL_GND_1_L_VL") (pintype "power_in"))
    )
    (net (code "11") (name "GNUB_3V3") (class "Default")
      (node (ref "JP64") (pin "13") (pinfunction "13_13") (pintype "passive"))
      (node (ref "SV3") (pin "13") (pinfunction "13_13") (pintype "passive"))
    )
    (net (code "12") (name "GNUB_GND") (class "Default")
      (node (ref "JP64") (pin "14") (pinfunction "14_14") (pintype "passive"))
      (node (ref "SV3") (pin "14") (pinfunction "14_14") (pintype "passive"))
    )
    (net (code "13") (name "GNUB_GPA0") (class "Default")
      (node (ref "JP64") (pin "1") (pinfunction "1_1") (pintype "passive"))
      (node (ref "SV3") (pin "1") (pinfunction "1_1") (pintype "passive"))
    )
    (net (code "14") (name "GNUB_GPA1") (class "Default")
      (node (ref "JP64") (pin "2") (pinfunction "2_2") (pintype "passive"))
      (node (ref "SV3") (pin "2") (pinfunction "2_2") (pintype "passive"))
    )
    (net (code "15") (name "GNUB_GPA3") (class "Default")
      (node (ref "JP64") (pin "3") (pinfunction "3_3") (pintype "passive"))
      (node (ref "SV3") (pin "3") (pinfunction "3_3") (pintype "passive"))
    )
    (net (code "16") (name "GNUB_GPIO11") (class "Default")
      (node (ref "JP64") (pin "12") (pinfunction "12_12") (pintype "passive"))
      (node (ref "SV3") (pin "12") (pinfunction "12_12") (pintype "passive"))
    )
    (net (code "17") (name "GNUB_GPIO14") (class "Default")
      (node (ref "JP64") (pin "11") (pinfunction "11_11") (pintype "passive"))
      (node (ref "SV3") (pin "11") (pinfunction "11_11") (pintype "passive"))
    )
    (net (code "18") (name "GNUB_MISO") (class "Default")
      (node (ref "JP64") (pin "8") (pinfunction "8_8") (pintype "passive"))
      (node (ref "SV3") (pin "8") (pinfunction "8_8") (pintype "passive"))
    )
    (net (code "19") (name "GNUB_MOSI") (class "Default")
      (node (ref "JP64") (pin "7") (pinfunction "7_7") (pintype "passive"))
      (node (ref "SV3") (pin "7") (pinfunction "7_7") (pintype "passive"))
    )
    (net (code "20") (name "GNUB_PWM_DATA") (class "Default")
      (node (ref "JP64") (pin "4") (pinfunction "4_4") (pintype "passive"))
      (node (ref "SV3") (pin "4") (pinfunction "4_4") (pintype "passive"))
    )
    (net (code "21") (name "GNUB_SCK") (class "Default")
      (node (ref "JP64") (pin "10") (pinfunction "10_10") (pintype "passive"))
      (node (ref "SV3") (pin "10") (pinfunction "10_10") (pintype "passive"))
    )
    (net (code "22") (name "GNUB_SCL") (class "Default")
      (node (ref "JP64") (pin "5") (pinfunction "5_5") (pintype "passive"))
      (node (ref "SV3") (pin "5") (pinfunction "5_5") (pintype "passive"))
    )
    (net (code "23") (name "GNUB_SDA") (class "Default")
      (node (ref "JP64") (pin "6") (pinfunction "6_6") (pintype "passive"))
      (node (ref "SV3") (pin "6") (pinfunction "6_6") (pintype "passive"))
    )
    (net (code "24") (name "GNUB_SYSCLOCK_0") (class "Default")
      (node (ref "JP64") (pin "9") (pinfunction "9_9") (pintype "passive"))
      (node (ref "SV3") (pin "9") (pinfunction "9_9") (pintype "passive"))
    )
    (net (code "25") (name "MOTOR_VCC") (class "Default")
      (node (ref "C5") (pin "1") (pinfunction "1_1") (pintype "passive"))
      (node (ref "C7") (pin "+") (pinfunction "+_+") (pintype "passive"))
      (node (ref "D1") (pin "C") (pinfunction "C_C") (pintype "passive"))
      (node (ref "D2") (pin "C") (pinfunction "C_C") (pintype "passive"))
      (node (ref "D5") (pin "C") (pinfunction "C_C") (pintype "passive"))
      (node (ref "D6") (pin "C") (pinfunction "C_C") (pintype "passive"))
      (node (ref "IC2") (pin "8") (pinfunction "VCC2_8") (pintype "power_in"))
      (node (ref "U$4") (pin "1") (pinfunction "1_1") (pintype "bidirectional"))
      (node (ref "X1") (pin "1") (pinfunction "1_1") (pintype "passive"))
    )
    (net (code "26") (name "Net-(IC1-I1)") (class "Default")
      (node (ref "IC1") (pin "1") (pinfunction "I1_1") (pintype "input"))
      (node (ref "JP26") (pin "1") (pinfunction "1_1") (pintype "passive"))
    )
    (net (code "27") (name "Net-(IC1-I2)") (class "Default")
      (node (ref "IC1") (pin "2") (pinfunction "I2_2") (pintype "input"))
      (node (ref "JP26") (pin "2") (pinfunction "2_2") (pintype "passive"))
    )
    (net (code "28") (name "Net-(IC1-I3)") (class "Default")
      (node (ref "IC1") (pin "3") (pinfunction "I3_3") (pintype "input"))
      (node (ref "JP26") (pin "3") (pinfunction "3_3") (pintype "passive"))
    )
    (net (code "29") (name "Net-(IC1-I4)") (class "Default")
      (node (ref "IC1") (pin "4") (pinfunction "I4_4") (pintype "input"))
      (node (ref "JP26") (pin "4") (pinfunction "4_4") (pintype "passive"))
    )
    (net (code "30") (name "Net-(IC1-I5)") (class "Default")
      (node (ref "IC1") (pin "5") (pinfunction "I5_5") (pintype "input"))
      (node (ref "JP26") (pin "5") (pinfunction "5_5") (pintype "passive"))
    )
    (net (code "31") (name "Net-(IC1-I6)") (class "Default")
      (node (ref "IC1") (pin "6") (pinfunction "I6_6") (pintype "input"))
      (node (ref "JP26") (pin "6") (pinfunction "6_6") (pintype "passive"))
    )
    (net (code "32") (name "Net-(IC1-I7)") (class "Default")
      (node (ref "IC1") (pin "7") (pinfunction "I7_7") (pintype "input"))
      (node (ref "JP26") (pin "7") (pinfunction "7_7") (pintype "passive"))
    )
    (net (code "33") (name "Net-(IC1-O1)") (class "Default")
      (node (ref "IC1") (pin "16") (pinfunction "O1_16") (pintype "open_collector"))
      (node (ref "JP21") (pin "1") (pinfunction "1_1") (pintype "passive"))
      (node (ref "JP25") (pin "2") (pinfunction "2_2") (pintype "passive"))
      (node (ref "R32") (pin "1") (pinfunction "1_1") (pintype "passive"))
    )
    (net (code "34") (name "Net-(IC1-O2)") (class "Default")
      (node (ref "IC1") (pin "15") (pinfunction "O2_15") (pintype "open_collector"))
      (node (ref "JP21") (pin "2") (pinfunction "2_2") (pintype "passive"))
      (node (ref "JP25") (pin "3") (pinfunction "3_3") (pintype "passive"))
      (node (ref "R34") (pin "1") (pinfunction "1_1") (pintype "passive"))
    )
    (net (code "35") (name "Net-(IC1-O3)") (class "Default")
      (node (ref "IC1") (pin "14") (pinfunction "O3_14") (pintype "open_collector"))
      (node (ref "JP21") (pin "3") (pinfunction "3_3") (pintype "passive"))
      (node (ref "JP25") (pin "4") (pinfunction "4_4") (pintype "passive"))
      (node (ref "R33") (pin "1") (pinfunction "1_1") (pintype "passive"))
    )
    (net (code "36") (name "Net-(IC1-O4)") (class "Default")
      (node (ref "IC1") (pin "13") (pinfunction "O4_13") (pintype "open_collector"))
      (node (ref "JP21") (pin "4") (pinfunction "4_4") (pintype "passive"))
      (node (ref "JP25") (pin "5") (pinfunction "5_5") (pintype "passive"))
      (node (ref "R35") (pin "1") (pinfunction "1_1") (pintype "passive"))
    )
    (net (code "37") (name "Net-(IC1-O5)") (class "Default")
      (node (ref "IC1") (pin "12") (pinfunction "O5_12") (pintype "open_collector"))
      (node (ref "JP21") (pin "5") (pinfunction "5_5") (pintype "passive"))
    )
    (net (code "38") (name "Net-(IC1-O6)") (class "Default")
      (node (ref "IC1") (pin "11") (pinfunction "O6_11") (pintype "open_collector"))
      (node (ref "JP21") (pin "6") (pinfunction "6_6") (pintype "passive"))
    )
    (net (code "39") (name "Net-(IC1-O7)") (class "Default")
      (node (ref "IC1") (pin "10") (pinfunction "O7_10") (pintype "open_collector"))
      (node (ref "JP21") (pin "7") (pinfunction "7_7") (pintype "passive"))
    )
    (net (code "40") (name "Net-(IC2-1Y)") (class "Default")
      (node (ref "D6") (pin "A") (pinfunction "A_A") (pintype "passive"))
      (node (ref "D8") (pin "C") (pinfunction "C_C") (pintype "passive"))
      (node (ref "IC2") (pin "3") (pinfunction "1Y_3") (pintype "output"))
      (node (ref "K2") (pin "1") (pinfunction "1_1") (pintype "passive"))
    )
    (net (code "41") (name "Net-(IC2-2Y)") (class "Default")
      (node (ref "D5") (pin "A") (pinfunction "A_A") (pintype "passive"))
      (node (ref "D7") (pin "C") (pinfunction "C_C") (pintype "passive"))
      (node (ref "IC2") (pin "6") (pinfunction "2Y_6") (pintype "output"))
      (node (ref "K2") (pin "2") (pinfunction "2_2") (pintype "passive"))
    )
    (net (code "42") (name "Net-(IC2-3Y)") (class "Default")
      (node (ref "D1") (pin "A") (pinfunction "A_A") (pintype "passive"))
      (node (ref "D3") (pin "C") (pinfunction "C_C") (pintype "passive"))
      (node (ref "IC2") (pin "11") (pinfunction "3Y_11") (pintype "output"))
      (node (ref "K1") (pin "1") (pinfunction "1_1") (pintype "passive"))
    )
    (net (code "43") (name "Net-(IC2-4Y)") (class "Default")
      (node (ref "D2") (pin "A") (pinfunction "A_A") (pintype "passive"))
      (node (ref "D4") (pin "C") (pinfunction "C_C") (pintype "passive"))
      (node (ref "IC2") (pin "14") (pinfunction "4Y_14") (pintype "output"))
      (node (ref "K1") (pin "2") (pinfunction "2_2") (pintype "passive"))
    )
    (net (code "44") (name "Net-(JP2-Pad1)") (class "Default")
      (node (ref "JP2") (pin "1") (pinfunction "1_1") (pintype "passive"))
      (node (ref "R19") (pin "1") (pinfunction "1_1") (pintype "passive"))
      (node (ref "SW1") (pin "A") (pinfunction "A_A") (pintype "passive"))
    )
    (net (code "45") (name "Net-(JP3-Pad1)") (class "Default")
      (node (ref "JP3") (pin "1") (pinfunction "1_1") (pintype "passive"))
      (node (ref "R18") (pin "2") (pinfunction "2_2") (pintype "passive"))
      (node (ref "SW1") (pin "B") (pinfunction "B_B") (pintype "passive"))
    )
    (net (code "46") (name "Net-(JP4-Pad2)") (class "Default")
      (node (ref "JP4") (pin "2") (pinfunction "2_2") (pintype "passive"))
      (node (ref "LED5") (pin "A") (pinfunction "A_A") (pintype "passive"))
    )
    (net (code "47") (name "Net-(JP5-Pad1)") (class "Default")
      (node (ref "JP5") (pin "1") (pinfunction "1_1") (pintype "passive"))
      (node (ref "LED1") (pin "A") (pinfunction "A_A") (pintype "passive"))
    )
    (net (code "48") (name "Net-(JP6-Pad1)") (class "Default")
      (node (ref "JP6") (pin "1") (pinfunction "1_1") (pintype "passive"))
      (node (ref "LED2") (pin "A") (pinfunction "A_A") (pintype "passive"))
    )
    (net (code "49") (name "Net-(JP7-Pad1)") (class "Default")
      (node (ref "JP7") (pin "1") (pinfunction "1_1") (pintype "passive"))
      (node (ref "LED3") (pin "A") (pinfunction "A_A") (pintype "passive"))
    )
    (net (code "50") (name "Net-(JP8-Pad1)") (class "Default")
      (node (ref "JP8") (pin "1") (pinfunction "1_1") (pintype "passive"))
      (node (ref "LED4") (pin "A") (pinfunction "A_A") (pintype "passive"))
    )
    (net (code "51") (name "Net-(JP14-Pad1)") (class "Default")
      (node (ref "JP14") (pin "1") (pinfunction "1_1") (pintype "passive"))
      (node (ref "R5") (pin "3") (pinfunction "3_3") (pintype "passive"))
    )
    (net (code "52") (name "Net-(JP15-Pad1)") (class "Default")
      (node (ref "JP15") (pin "1") (pinfunction "1_1") (pintype "passive"))
      (node (ref "R5") (pin "2") (pinfunction "2_2") (pintype "passive"))
    )
    (net (code "53") (name "Net-(JP16-Pad1)") (class "Default")
      (node (ref "JP16") (pin "1") (pinfunction "1_1") (pintype "passive"))
      (node (ref "R5") (pin "1") (pinfunction "1_1") (pintype "passive"))
    )
    (net (code "54") (name "Net-(JP17-Pad1)") (class "Default")
      (node (ref "JP17") (pin "1") (pinfunction "1_1") (pintype "passive"))
      (node (ref "R21") (pin "2") (pinfunction "2_2") (pintype "passive"))
    )
    (net (code "55") (name "Net-(JP22-Pad1)") (class "Default")
      (node (ref "JP22") (pin "1") (pinfunction "1_1") (pintype "passive"))
      (node (ref "R31") (pin "1") (pinfunction "1_1") (pintype "passive"))
    )
    (net (code "56") (name "Net-(JP22-Pad2)") (class "Default")
      (node (ref "JP22") (pin "2") (pinfunction "2_2") (pintype "passive"))
      (node (ref "R30") (pin "1") (pinfunction "1_1") (pintype "passive"))
    )
    (net (code "57") (name "Net-(JP22-Pad3)") (class "Default")
      (node (ref "JP22") (pin "3") (pinfunction "3_3") (pintype "passive"))
      (node (ref "R29") (pin "1") (pinfunction "1_1") (pintype "passive"))
    )
    (net (code "58") (name "Net-(JP22-Pad4)") (class "Default")
      (node (ref "JP22") (pin "4") (pinfunction "4_4") (pintype "passive"))
      (node (ref "R28") (pin "1") (pinfunction "1_1") (pintype "passive"))
    )
    (net (code "59") (name "Net-(JP22-Pad5)") (class "Default")
      (node (ref "JP22") (pin "5") (pinfunction "5_5") (pintype "passive"))
      (node (ref "R27") (pin "1") (pinfunction "1_1") (pintype "passive"))
    )
    (net (code "60") (name "Net-(JP22-Pad6)") (class "Default")
      (node (ref "JP22") (pin "6") (pinfunction "6_6") (pintype "passive"))
      (node (ref "R26") (pin "1") (pinfunction "1_1") (pintype "passive"))
    )
    (net (code "61") (name "Net-(JP22-Pad7)") (class "Default")
      (node (ref "JP22") (pin "7") (pinfunction "7_7") (pintype "passive"))
      (node (ref "R25") (pin "1") (pinfunction "1_1") (pintype "passive"))
    )
    (net (code "62") (name "Net-(JP22-Pad8)") (class "Default")
      (node (ref "JP22") (pin "8") (pinfunction "8_8") (pintype "passive"))
      (node (ref "R24") (pin "1") (pinfunction "1_1") (pintype "passive"))
    )
    (net (code "63") (name "Net-(JP23-Pad1)") (class "Default")
      (node (ref "JP23") (pin "1") (pinfunction "1_1") (pintype "passive"))
      (node (ref "LED8") (pin "1") (pinfunction "A_1") (pintype "passive"))
      (node (ref "LED8") (pin "6") (pinfunction "A_6") (pintype "passive"))
    )
    (net (code "64") (name "Net-(JP24-Pad1)") (class "Default")
      (node (ref "JP24") (pin "1") (pinfunction "1_1") (pintype "passive"))
      (node (ref "JP27") (pin "4") (pinfunction "4_4") (pintype "passive"))
    )
    (net (code "65") (name "Net-(JP24-Pad2)") (class "Default")
      (node (ref "JP24") (pin "2") (pinfunction "2_2") (pintype "passive"))
      (node (ref "JP27") (pin "3") (pinfunction "3_3") (pintype "passive"))
    )
    (net (code "66") (name "Net-(JP24-Pad3)") (class "Default")
      (node (ref "JP24") (pin "3") (pinfunction "3_3") (pintype "passive"))
      (node (ref "JP27") (pin "2") (pinfunction "2_2") (pintype "passive"))
    )
    (net (code "67") (name "Net-(JP24-Pad4)") (class "Default")
      (node (ref "JP24") (pin "4") (pinfunction "4_4") (pintype "passive"))
      (node (ref "JP27") (pin "1") (pinfunction "1_1") (pintype "passive"))
    )
    (net (code "68") (name "Net-(JP44-Pad1)") (class "Default")
      (node (ref "JP44") (pin "1") (pinfunction "1_1") (pintype "passive"))
      (node (ref "JP44") (pin "2") (pinfunction "2_2") (pintype "passive"))
      (node (ref "JP44") (pin "3") (pinfunction "3_3") (pintype "passive"))
      (node (ref "JP44") (pin "4") (pinfunction "4_4") (pintype "passive"))
      (node (ref "JP44") (pin "5") (pinfunction "5_5") (pintype "passive"))
      (node (ref "JP44") (pin "6") (pinfunction "6_6") (pintype "passive"))
      (node (ref "JP44") (pin "7") (pinfunction "7_7") (pintype "passive"))
      (node (ref "JP44") (pin "8") (pinfunction "8_8") (pintype "passive"))
    )
    (net (code "69") (name "Net-(JP45-Pad1)") (class "Default")
      (node (ref "JP45") (pin "1") (pinfunction "1_1") (pintype "passive"))
      (node (ref "JP45") (pin "2") (pinfunction "2_2") (pintype "passive"))
      (node (ref "JP45") (pin "3") (pinfunction "3_3") (pintype "passive"))
      (node (ref "JP45") (pin "4") (pinfunction "4_4") (pintype "passive"))
      (node (ref "JP45") (pin "5") (pinfunction "5_5") (pintype "passive"))
      (node (ref "JP45") (pin "6") (pinfunction "6_6") (pintype "passive"))
      (node (ref "JP45") (pin "7") (pinfunction "7_7") (pintype "passive"))
      (node (ref "JP45") (pin "8") (pinfunction "8_8") (pintype "passive"))
    )
    (net (code "70") (name "Net-(JP49-Pad1)") (class "Default")
      (node (ref "JP49") (pin "1") (pinfunction "1_1") (pintype "passive"))
      (node (ref "JP50") (pin "3") (pinfunction "3_3") (pintype "passive"))
    )
    (net (code "71") (name "Net-(JP49-Pad2)") (class "Default")
      (node (ref "JP49") (pin "2") (pinfunction "2_2") (pintype "passive"))
      (node (ref "JP50") (pin "2") (pinfunction "2_2") (pintype "passive"))
    )
    (net (code "72") (name "Net-(JP49-Pad3)") (class "Default")
      (node (ref "JP49") (pin "3") (pinfunction "3_3") (pintype "passive"))
      (node (ref "JP50") (pin "1") (pinfunction "1_1") (pintype "passive"))
    )
    (net (code "73") (name "Net-(JP51-Pad1)") (class "Default")
      (node (ref "JP51") (pin "1") (pinfunction "1_1") (pintype "passive"))
      (node (ref "JP52") (pin "3") (pinfunction "3_3") (pintype "passive"))
    )
    (net (code "74") (name "Net-(JP51-Pad2)") (class "Default")
      (node (ref "JP51") (pin "2") (pinfunction "2_2") (pintype "passive"))
      (node (ref "JP52") (pin "2") (pinfunction "2_2") (pintype "passive"))
    )
    (net (code "75") (name "Net-(JP51-Pad3)") (class "Default")
      (node (ref "JP51") (pin "3") (pinfunction "3_3") (pintype "passive"))
      (node (ref "JP52") (pin "1") (pinfunction "1_1") (pintype "passive"))
    )
    (net (code "76") (name "Net-(JP56-Pad1)") (class "Default")
      (node (ref "JP56") (pin "1") (pinfunction "1_1") (pintype "passive"))
      (node (ref "JP56") (pin "2") (pinfunction "2_2") (pintype "passive"))
    )
    (net (code "77") (name "Net-(JP56-Pad3)") (class "Default")
      (node (ref "JP56") (pin "3") (pinfunction "3_3") (pintype "passive"))
      (node (ref "JP56") (pin "4") (pinfunction "4_4") (pintype "passive"))
    )
    (net (code "78") (name "Net-(JP56-Pad5)") (class "Default")
      (node (ref "JP56") (pin "5") (pinfunction "5_5") (pintype "passive"))
      (node (ref "JP56") (pin "6") (pinfunction "6_6") (pintype "passive"))
    )
    (net (code "79") (name "Net-(JP56-Pad7)") (class "Default")
      (node (ref "JP56") (pin "7") (pinfunction "7_7") (pintype "passive"))
      (node (ref "JP56") (pin "8") (pinfunction "8_8") (pintype "passive"))
    )
    (net (code "80") (name "Net-(JP56-Pad10)") (class "Default")
      (node (ref "JP56") (pin "10") (pinfunction "10_10") (pintype "passive"))
      (node (ref "JP56") (pin "9") (pinfunction "9_9") (pintype "passive"))
    )
    (net (code "81") (name "Net-(JP56-Pad11)") (class "Default")
      (node (ref "JP56") (pin "11") (pinfunction "11_11") (pintype "passive"))
      (node (ref "JP56") (pin "12") (pinfunction "12_12") (pintype "passive"))
    )
    (net (code "82") (name "Net-(JP56-Pad13)") (class "Default")
      (node (ref "JP56") (pin "13") (pinfunction "13_13") (pintype "passive"))
      (node (ref "JP56") (pin "14") (pinfunction "14_14") (pintype "passive"))
    )
    (net (code "83") (name "Net-(JP56-Pad15)") (class "Default")
      (node (ref "JP56") (pin "15") (pinfunction "15_15") (pintype "passive"))
      (node (ref "JP56") (pin "16") (pinfunction "16_16") (pintype "passive"))
    )
    (net (code "84") (name "Net-(JP56-Pad17)") (class "Default")
      (node (ref "JP56") (pin "17") (pinfunction "17_17") (pintype "passive"))
      (node (ref "JP56") (pin "18") (pinfunction "18_18") (pintype "passive"))
    )
    (net (code "85") (name "Net-(JP59-Pad2)") (class "Default")
      (node (ref "JP59") (pin "2") (pinfunction "2_2") (pintype "passive"))
      (node (ref "R17") (pin "1") (pinfunction "1_1") (pintype "passive"))
    )
    (net (code "86") (name "Net-(JP60-Pad2)") (class "Default")
      (node (ref "JP60") (pin "2") (pinfunction "2_2") (pintype "passive"))
      (node (ref "R16") (pin "1") (pinfunction "1_1") (pintype "passive"))
    )
    (net (code "87") (name "Net-(JP61-Pad2)") (class "Default")
      (node (ref "JP61") (pin "2") (pinfunction "2_2") (pintype "passive"))
      (node (ref "R15") (pin "1") (pinfunction "1_1") (pintype "passive"))
    )
    (net (code "88") (name "Net-(JP62-Pad2)") (class "Default")
      (node (ref "JP62") (pin "2") (pinfunction "2_2") (pintype "passive"))
      (node (ref "R14") (pin "1") (pinfunction "1_1") (pintype "passive"))
    )
    (net (code "89") (name "Net-(JP65-Pad1)") (class "Default")
      (node (ref "JP65") (pin "1") (pinfunction "1_1") (pintype "passive"))
      (node (ref "JP65") (pin "2") (pinfunction "2_2") (pintype "passive"))
      (node (ref "R23") (pin "1") (pinfunction "1_1") (pintype "passive"))
    )
    (net (code "90") (name "Net-(JP66-Pad1)") (class "Default")
      (node (ref "JP66") (pin "1") (pinfunction "1_1") (pintype "passive"))
      (node (ref "JP66") (pin "2") (pinfunction "2_2") (pintype "passive"))
      (node (ref "R22") (pin "1") (pinfunction "1_1") (pintype "passive"))
    )
    (net (code "91") (name "Net-(JP68-Pad1)") (class "Default")
      (node (ref "JP68") (pin "1") (pinfunction "1_1") (pintype "passive"))
      (node (ref "JP68") (pin "2") (pinfunction "2_2") (pintype "passive"))
      (node (ref "JP68") (pin "3") (pinfunction "3_3") (pintype "passive"))
      (node (ref "JP68") (pin "4") (pinfunction "4_4") (pintype "passive"))
      (node (ref "JP68") (pin "5") (pinfunction "5_5") (pintype "passive"))
      (node (ref "JP68") (pin "6") (pinfunction "6_6") (pintype "passive"))
      (node (ref "JP68") (pin "7") (pinfunction "7_7") (pintype "passive"))
      (node (ref "JP68") (pin "8") (pinfunction "8_8") (pintype "passive"))
    )
    (net (code "92") (name "Net-(JP69-Pad1)") (class "Default")
      (node (ref "JP69") (pin "1") (pinfunction "1_1") (pintype "passive"))
      (node (ref "JP69") (pin "2") (pinfunction "2_2") (pintype "passive"))
      (node (ref "JP69") (pin "3") (pinfunction "3_3") (pintype "passive"))
      (node (ref "JP69") (pin "4") (pinfunction "4_4") (pintype "passive"))
      (node (ref "JP69") (pin "5") (pinfunction "5_5") (pintype "passive"))
      (node (ref "JP69") (pin "6") (pinfunction "6_6") (pintype "passive"))
      (node (ref "JP69") (pin "7") (pinfunction "7_7") (pintype "passive"))
      (node (ref "JP69") (pin "8") (pinfunction "8_8") (pintype "passive"))
    )
    (net (code "93") (name "Net-(JP72-Pad1)") (class "Default")
      (node (ref "JP72") (pin "1") (pinfunction "1_1") (pintype "passive"))
      (node (ref "LED6") (pin "1") (pinfunction "A_1") (pintype "passive"))
      (node (ref "LED6") (pin "6") (pinfunction "A_6") (pintype "passive"))
    )
    (net (code "94") (name "Net-(JP73-Pad1)") (class "Default")
      (node (ref "JP73") (pin "1") (pinfunction "1_1") (pintype "passive"))
      (node (ref "LED7") (pin "1") (pinfunction "A_1") (pintype "passive"))
      (node (ref "LED7") (pin "6") (pinfunction "A_6") (pintype "passive"))
    )
    (net (code "95") (name "Net-(LCD1-A1+)") (class "Default")
      (node (ref "LCD1") (pin "1") (pinfunction "A1+_1") (pintype "bidirectional"))
      (node (ref "R8") (pin "1") (pinfunction "1_1") (pintype "passive"))
    )
    (net (code "96") (name "Net-(LCD1-A2+)") (class "Default")
      (node (ref "LCD1") (pin "20") (pinfunction "A2+_20") (pintype "bidirectional"))
      (node (ref "R7") (pin "1") (pinfunction "1_1") (pintype "passive"))
    )
    (net (code "97") (name "Net-(LCD1-CAP1N)") (class "Default")
      (node (ref "C2") (pin "1") (pinfunction "1_1") (pintype "passive"))
      (node (ref "LCD1") (pin "21") (pinfunction "CAP1N_21") (pintype "bidirectional"))
    )
    (net (code "98") (name "Net-(LCD1-CAP1P)") (class "Default")
      (node (ref "C2") (pin "2") (pinfunction "2_2") (pintype "passive"))
      (node (ref "LCD1") (pin "22") (pinfunction "CAP1P_22") (pintype "bidirectional"))
    )
    (net (code "99") (name "Net-(LCD1-D0)") (class "Default")
      (node (ref "LCD1") (pin "30") (pinfunction "D5_30") (pintype "bidirectional"))
      (node (ref "LCD1") (pin "31") (pinfunction "D4_31") (pintype "bidirectional"))
      (node (ref "LCD1") (pin "32") (pinfunction "D3_32") (pintype "bidirectional"))
      (node (ref "LCD1") (pin "33") (pinfunction "D2_33") (pintype "bidirectional"))
      (node (ref "LCD1") (pin "34") (pinfunction "D1_34") (pintype "bidirectional"))
      (node (ref "LCD1") (pin "35") (pinfunction "D0_35") (pintype "bidirectional"))
      (node (ref "LCD1") (pin "36") (pinfunction "E_36") (pintype "bidirectional"))
      (node (ref "LCD1") (pin "37") (pinfunction "R/W_37") (pintype "bidirectional"))
      (node (ref "LCD1") (pin "40") (pinfunction "RESET_40") (pintype "bidirectional"))
      (node (ref "R10") (pin "1") (pinfunction "1_1") (pintype "passive"))
    )
    (net (code "100") (name "Net-(LCD1-VOUT)") (class "Default")
      (node (ref "C3") (pin "2") (pinfunction "2_2") (pintype "passive"))
      (node (ref "LCD1") (pin "24") (pinfunction "VOUT_24") (pintype "bidirectional"))
    )
    (net (code "101") (name "Net-(LED1-C)") (class "Default")
      (node (ref "LED1") (pin "K") (pinfunction "C_K") (pintype "passive"))
      (node (ref "R1") (pin "2") (pinfunction "2_2") (pintype "passive"))
    )
    (net (code "102") (name "Net-(LED2-C)") (class "Default")
      (node (ref "LED2") (pin "K") (pinfunction "C_K") (pintype "passive"))
      (node (ref "R2") (pin "2") (pinfunction "2_2") (pintype "passive"))
    )
    (net (code "103") (name "Net-(LED3-C)") (class "Default")
      (node (ref "LED3") (pin "K") (pinfunction "C_K") (pintype "passive"))
      (node (ref "R3") (pin "2") (pinfunction "2_2") (pintype "passive"))
    )
    (net (code "104") (name "Net-(LED4-C)") (class "Default")
      (node (ref "LED4") (pin "K") (pinfunction "C_K") (pintype "passive"))
      (node (ref "R4") (pin "2") (pinfunction "2_2") (pintype "passive"))
    )
    (net (code "105") (name "Net-(LED5-C)") (class "Default")
      (node (ref "LED5") (pin "K") (pinfunction "C_K") (pintype "passive"))
      (node (ref "R6") (pin "1") (pinfunction "1_1") (pintype "passive"))
    )
    (net (code "106") (name "Net-(LED6-A-Pad10)") (class "Default")
      (node (ref "LED6") (pin "10") (pinfunction "A_10") (pintype "passive"))
      (node (ref "LED7") (pin "10") (pinfunction "A_10") (pintype "passive"))
      (node (ref "LED8") (pin "10") (pinfunction "A_10") (pintype "passive"))
      (node (ref "R24") (pin "2") (pinfunction "2_2") (pintype "passive"))
    )
    (net (code "107") (name "Net-(LED6-B)") (class "Default")
      (node (ref "LED6") (pin "9") (pinfunction "B_9") (pintype "passive"))
      (node (ref "LED7") (pin "9") (pinfunction "B_9") (pintype "passive"))
      (node (ref "LED8") (pin "9") (pinfunction "B_9") (pintype "passive"))
      (node (ref "R25") (pin "2") (pinfunction "2_2") (pintype "passive"))
    )
    (net (code "108") (name "Net-(LED6-C)") (class "Default")
      (node (ref "LED6") (pin "8") (pinfunction "C_8") (pintype "passive"))
      (node (ref "LED7") (pin "8") (pinfunction "C_8") (pintype "passive"))
      (node (ref "LED8") (pin "8") (pinfunction "C_8") (pintype "passive"))
      (node (ref "R26") (pin "2") (pinfunction "2_2") (pintype "passive"))
    )
    (net (code "109") (name "Net-(LED6-D)") (class "Default")
      (node (ref "LED6") (pin "5") (pinfunction "D_5") (pintype "passive"))
      (node (ref "LED7") (pin "5") (pinfunction "D_5") (pintype "passive"))
      (node (ref "LED8") (pin "5") (pinfunction "D_5") (pintype "passive"))
      (node (ref "R27") (pin "2") (pinfunction "2_2") (pintype "passive"))
    )
    (net (code "110") (name "Net-(LED6-DP)") (class "Default")
      (node (ref "LED6") (pin "7") (pinfunction "DP_7") (pintype "passive"))
      (node (ref "LED7") (pin "7") (pinfunction "DP_7") (pintype "passive"))
      (node (ref "LED8") (pin "7") (pinfunction "DP_7") (pintype "passive"))
      (node (ref "R31") (pin "2") (pinfunction "2_2") (pintype "passive"))
    )
    (net (code "111") (name "Net-(LED6-E)") (class "Default")
      (node (ref "LED6") (pin "4") (pinfunction "E_4") (pintype "passive"))
      (node (ref "LED7") (pin "4") (pinfunction "E_4") (pintype "passive"))
      (node (ref "LED8") (pin "4") (pinfunction "E_4") (pintype "passive"))
      (node (ref "R28") (pin "2") (pinfunction "2_2") (pintype "passive"))
    )
    (net (code "112") (name "Net-(LED6-F)") (class "Default")
      (node (ref "LED6") (pin "2") (pinfunction "F_2") (pintype "passive"))
      (node (ref "LED7") (pin "2") (pinfunction "F_2") (pintype "passive"))
      (node (ref "LED8") (pin "2") (pinfunction "F_2") (pintype "passive"))
      (node (ref "R29") (pin "2") (pinfunction "2_2") (pintype "passive"))
    )
    (net (code "113") (name "Net-(LED6-G)") (class "Default")
      (node (ref "LED6") (pin "3") (pinfunction "G_3") (pintype "passive"))
      (node (ref "LED7") (pin "3") (pinfunction "G_3") (pintype "passive"))
      (node (ref "LED8") (pin "3") (pinfunction "G_3") (pintype "passive"))
      (node (ref "R30") (pin "2") (pinfunction "2_2") (pintype "passive"))
    )
    (net (code "114") (name "Net-(LED9-C)") (class "Default")
      (node (ref "LED9") (pin "K") (pinfunction "C_K") (pintype "passive"))
      (node (ref "R32") (pin "2") (pinfunction "2_2") (pintype "passive"))
    )
    (net (code "115") (name "Net-(LED10-C)") (class "Default")
      (node (ref "LED10") (pin "K") (pinfunction "C_K") (pintype "passive"))
      (node (ref "R34") (pin "2") (pinfunction "2_2") (pintype "passive"))
    )
    (net (code "116") (name "Net-(LED11-C)") (class "Default")
      (node (ref "LED11") (pin "K") (pinfunction "C_K") (pintype "passive"))
      (node (ref "R33") (pin "2") (pinfunction "2_2") (pintype "passive"))
    )
    (net (code "117") (name "Net-(LED12-C)") (class "Default")
      (node (ref "LED12") (pin "K") (pinfunction "C_K") (pintype "passive"))
      (node (ref "R35") (pin "2") (pinfunction "2_2") (pintype "passive"))
    )
    (net (code "118") (name "Net-(S1-P)") (class "Default")
      (node (ref "JP62") (pin "3") (pinfunction "3_3") (pintype "passive"))
      (node (ref "JP9") (pin "1") (pinfunction "1_1") (pintype "passive"))
      (node (ref "S1") (pin "3") (pinfunction "P_3") (pintype "passive"))
      (node (ref "S1") (pin "4") (pinfunction "P1_4") (pintype "passive"))
    )
    (net (code "119") (name "Net-(S2-P)") (class "Default")
      (node (ref "JP10") (pin "1") (pinfunction "1_1") (pintype "passive"))
      (node (ref "JP61") (pin "3") (pinfunction "3_3") (pintype "passive"))
      (node (ref "S2") (pin "3") (pinfunction "P_3") (pintype "passive"))
      (node (ref "S2") (pin "4") (pinfunction "P1_4") (pintype "passive"))
    )
    (net (code "120") (name "Net-(S3-P)") (class "Default")
      (node (ref "JP11") (pin "1") (pinfunction "1_1") (pintype "passive"))
      (node (ref "JP60") (pin "3") (pinfunction "3_3") (pintype "passive"))
      (node (ref "S3") (pin "3") (pinfunction "P_3") (pintype "passive"))
      (node (ref "S3") (pin "4") (pinfunction "P1_4") (pintype "passive"))
    )
    (net (code "121") (name "Net-(S4-P)") (class "Default")
      (node (ref "JP12") (pin "1") (pinfunction "1_1") (pintype "passive"))
      (node (ref "JP59") (pin "3") (pinfunction "3_3") (pintype "passive"))
      (node (ref "S4") (pin "3") (pinfunction "P_3") (pintype "passive"))
      (node (ref "S4") (pin "4") (pinfunction "P1_4") (pintype "passive"))
    )
    (net (code "122") (name "Net-(SP1-1)") (class "Default")
      (node (ref "SP1") (pin "-") (pinfunction "1_-") (pintype "passive"))
      (node (ref "T1") (pin "3") (pinfunction "C_3") (pintype "passive"))
    )
    (net (code "123") (name "Net-(SW1B-2)") (class "Default")
      (node (ref "JP13") (pin "1") (pinfunction "1_1") (pintype "passive"))
      (node (ref "R20") (pin "2") (pinfunction "2_2") (pintype "passive"))
      (node (ref "SW1") (pin "E") (pinfunction "2_E") (pintype "passive"))
    )
    (net (code "124") (name "Net-(T1-B)") (class "Default")
      (node (ref "R21") (pin "1") (pinfunction "1_1") (pintype "passive"))
      (node (ref "T1") (pin "2") (pinfunction "B_2") (pintype "passive"))
    )
    (net (code "125") (name "Net-(U$2-CTS)") (class "Default")
      (node (ref "JP38") (pin "1") (pinfunction "1_1") (pintype "passive"))
      (node (ref "U$2") (pin "5") (pinfunction "CTS_5") (pintype "bidirectional"))
    )
    (net (code "126") (name "Net-(U$2-DCD)") (class "Default")
      (node (ref "JP36") (pin "1") (pinfunction "1_1") (pintype "passive"))
      (node (ref "U$2") (pin "1") (pinfunction "DCD_1") (pintype "bidirectional"))
    )
    (net (code "127") (name "Net-(U$2-DSR)") (class "Default")
      (node (ref "JP36") (pin "3") (pinfunction "3_3") (pintype "passive"))
      (node (ref "U$2") (pin "3") (pinfunction "DSR_3") (pintype "bidirectional"))
    )
    (net (code "128") (name "Net-(U$2-DTR)") (class "Default")
      (node (ref "JP36") (pin "2") (pinfunction "2_2") (pintype "passive"))
      (node (ref "U$2") (pin "2") (pinfunction "DTR_2") (pintype "bidirectional"))
    )
    (net (code "129") (name "Net-(U$2-GND)") (class "Default")
      (node (ref "JP38") (pin "2") (pinfunction "2_2") (pintype "passive"))
      (node (ref "U$2") (pin "6") (pinfunction "GND_6") (pintype "bidirectional"))
    )
    (net (code "130") (name "Net-(U$2-RI)") (class "Default")
      (node (ref "JP37") (pin "3") (pinfunction "3_3") (pintype "passive"))
      (node (ref "U$2") (pin "13") (pinfunction "RI_13") (pintype "bidirectional"))
    )
    (net (code "131") (name "Net-(U$2-RST_N)") (class "Default")
      (node (ref "JP37") (pin "2") (pinfunction "2_2") (pintype "passive"))
      (node (ref "U$2") (pin "12") (pinfunction "RST_N_12") (pintype "bidirectional"))
    )
    (net (code "132") (name "Net-(U$2-RTS)") (class "Default")
      (node (ref "JP36") (pin "4") (pinfunction "4_4") (pintype "passive"))
      (node (ref "U$2") (pin "4") (pinfunction "RTS_4") (pintype "bidirectional"))
    )
    (net (code "133") (name "Net-(U$2-RX)") (class "Default")
      (node (ref "JP38") (pin "5") (pinfunction "5_5") (pintype "passive"))
      (node (ref "U$2") (pin "9") (pinfunction "RX_9") (pintype "bidirectional"))
    )
    (net (code "134") (name "Net-(U$2-SUSPEND)") (class "Default")
      (node (ref "JP38") (pin "6") (pinfunction "6_6") (pintype "passive"))
      (node (ref "U$2") (pin "10") (pinfunction "SUSPEND_10") (pintype "bidirectional"))
    )
    (net (code "135") (name "Net-(U$2-SUSPEND_N)") (class "Default")
      (node (ref "JP37") (pin "1") (pinfunction "1_1") (pintype "passive"))
      (node (ref "U$2") (pin "11") (pinfunction "SUSPEND_N_11") (pintype "bidirectional"))
    )
    (net (code "136") (name "Net-(U$2-TX)") (class "Default")
      (node (ref "JP38") (pin "3") (pinfunction "3_3") (pintype "passive"))
      (node (ref "U$2") (pin "7") (pinfunction "TX_7") (pintype "bidirectional"))
    )
    (net (code "137") (name "Net-(U$2-VBUS)") (class "Default")
      (node (ref "JP38") (pin "4") (pinfunction "4_4") (pintype "passive"))
      (node (ref "U$2") (pin "8") (pinfunction "VBUS_8") (pintype "bidirectional"))
    )
    (net (code "138") (name "Net-(U$2-VDD)") (class "Default")
      (node (ref "JP37") (pin "4") (pinfunction "4_4") (pintype "passive"))
      (node (ref "U$2") (pin "14") (pinfunction "VDD_14") (pintype "bidirectional"))
    )
    (net (code "139") (name "Net-(U$4-COMM(2))") (class "Default")
      (node (ref "3V3") (pin "VIN") (pinfunction "VIN_VIN") (pintype "bidirectional"))
      (node (ref "5V") (pin "VIN") (pinfunction "VIN_VIN") (pintype "bidirectional"))
      (node (ref "U$4") (pin "2") (pinfunction "COMM(2)_2") (pintype "bidirectional"))
    )
    (net (code "140") (name "Net-(U$5-AUD)") (class "Default")
      (node (ref "JP30") (pin "3") (pinfunction "3_3") (pintype "passive"))
      (node (ref "U$5") (pin "1") (pinfunction "AUD_1") (pintype "bidirectional"))
    )
    (net (code "141") (name "Net-(U$5-GND)") (class "Default")
      (node (ref "JP30") (pin "2") (pinfunction "2_2") (pintype "passive"))
      (node (ref "U$5") (pin "2") (pinfunction "GND_2") (pintype "bidirectional"))
    )
    (net (code "142") (name "Net-(U$5-VCC)") (class "Default")
      (node (ref "JP30") (pin "1") (pinfunction "1_1") (pintype "passive"))
      (node (ref "U$5") (pin "3") (pinfunction "VCC_3") (pintype "bidirectional"))
    )
    (net (code "143") (name "Net-(U$6-1)") (class "Default")
      (node (ref "JP43") (pin "1") (pinfunction "1_1") (pintype "passive"))
      (node (ref "U$6") (pin "2") (pinfunction "1_2") (pintype "bidirectional"))
    )
    (net (code "144") (name "Net-(U$6-2)") (class "Default")
      (node (ref "JP43") (pin "2") (pinfunction "2_2") (pintype "passive"))
      (node (ref "U$6") (pin "1") (pinfunction "2_1") (pintype "bidirectional"))
    )
    (net (code "145") (name "Net-(U$7-2)") (class "Default")
      (node (ref "U$4") (pin "3") (pinfunction "3_3") (pintype "bidirectional"))
      (node (ref "U$7") (pin "1") (pinfunction "2_1") (pintype "bidirectional"))
    )
    (net (code "146") (name "Net-(U$9-GND)") (class "Default")
      (node (ref "JP33") (pin "3") (pinfunction "3_3") (pintype "passive"))
      (node (ref "U$9") (pin "3") (pinfunction "GND_3") (pintype "bidirectional"))
    )
    (net (code "147") (name "Net-(U$9-IN+)") (class "Default")
      (node (ref "JP31") (pin "1") (pinfunction "1_1") (pintype "passive"))
      (node (ref "U$9") (pin "6") (pinfunction "IN+_6") (pintype "bidirectional"))
    )
    (net (code "148") (name "Net-(U$9-IN-)") (class "Default")
      (node (ref "JP31") (pin "2") (pinfunction "2_2") (pintype "passive"))
      (node (ref "U$9") (pin "7") (pinfunction "IN-_7") (pintype "bidirectional"))
    )
    (net (code "149") (name "Net-(U$9-OUT+)") (class "Default")
      (node (ref "JP32") (pin "2") (pinfunction "2_2") (pintype "passive"))
      (node (ref "U$9") (pin "1") (pinfunction "OUT+_1") (pintype "bidirectional"))
    )
    (net (code "150") (name "Net-(U$9-OUT-)") (class "Default")
      (node (ref "JP32") (pin "1") (pinfunction "1_1") (pintype "passive"))
      (node (ref "U$9") (pin "2") (pinfunction "OUT-_2") (pintype "bidirectional"))
    )
    (net (code "151") (name "Net-(U$9-PWR)") (class "Default")
      (node (ref "JP33") (pin "2") (pinfunction "2_2") (pintype "passive"))
      (node (ref "U$9") (pin "4") (pinfunction "PWR_4") (pintype "bidirectional"))
    )
    (net (code "152") (name "Net-(U$9-SDN)") (class "Default")
      (node (ref "JP33") (pin "1") (pinfunction "1_1") (pintype "passive"))
      (node (ref "U$9") (pin "5") (pinfunction "SDN_5") (pintype "bidirectional"))
    )
    (net (code "153") (name "Net-(U$9-VOL+)") (class "Default")
      (node (ref "JP34") (pin "3") (pinfunction "3_3") (pintype "passive"))
      (node (ref "U$9") (pin "10") (pinfunction "VOL+_10") (pintype "bidirectional"))
    )
    (net (code "154") (name "Net-(U$9-VOL-)") (class "Default")
      (node (ref "JP34") (pin "1") (pinfunction "1_1") (pintype "passive"))
      (node (ref "U$9") (pin "8") (pinfunction "VOL-_8") (pintype "bidirectional"))
    )
    (net (code "155") (name "Net-(U$9-VOL->)") (class "Default")
      (node (ref "JP34") (pin "2") (pinfunction "2_2") (pintype "passive"))
      (node (ref "U$9") (pin "9") (pinfunction "VOL->_9") (pintype "bidirectional"))
    )
    (net (code "156") (name "Net-(U$10-CLK)") (class "Default")
      (node (ref "JP35") (pin "4") (pinfunction "4_4") (pintype "passive"))
      (node (ref "U$10") (pin "4") (pinfunction "CLK_4") (pintype "bidirectional"))
    )
    (net (code "157") (name "Net-(U$10-GND)") (class "Default")
      (node (ref "JP35") (pin "7") (pinfunction "7_7") (pintype "passive"))
      (node (ref "U$10") (pin "1") (pinfunction "GND_1") (pintype "bidirectional"))
    )
    (net (code "158") (name "Net-(U$10-MISO)") (class "Default")
      (node (ref "JP35") (pin "3") (pinfunction "3_3") (pintype "passive"))
      (node (ref "U$10") (pin "5") (pinfunction "MISO_5") (pintype "bidirectional"))
    )
    (net (code "159") (name "Net-(U$10-MOSI)") (class "Default")
      (node (ref "JP35") (pin "2") (pinfunction "2_2") (pintype "passive"))
      (node (ref "U$10") (pin "6") (pinfunction "MOSI_6") (pintype "bidirectional"))
    )
    (net (code "160") (name "Net-(U$10-SQW)") (class "Default")
      (node (ref "JP35") (pin "5") (pinfunction "5_5") (pintype "passive"))
      (node (ref "U$10") (pin "3") (pinfunction "SQW_3") (pintype "bidirectional"))
    )
    (net (code "161") (name "Net-(U$10-SS)") (class "Default")
      (node (ref "JP35") (pin "1") (pinfunction "1_1") (pintype "passive"))
      (node (ref "U$10") (pin "7") (pinfunction "SS_7") (pintype "bidirectional"))
    )
    (net (code "162") (name "Net-(U$10-VCC)") (class "Default")
      (node (ref "JP35") (pin "6") (pinfunction "6_6") (pintype "passive"))
      (node (ref "U$10") (pin "2") (pinfunction "VCC_2") (pintype "bidirectional"))
    )
    (net (code "163") (name "Net-(U$12-CD)") (class "Default")
      (node (ref "JP39") (pin "1") (pinfunction "1_1") (pintype "passive"))
      (node (ref "U$12") (pin "7") (pinfunction "CD_7") (pintype "bidirectional"))
    )
    (net (code "164") (name "Net-(U$12-CS)") (class "Default")
      (node (ref "JP39") (pin "7") (pinfunction "7_7") (pintype "passive"))
      (node (ref "U$12") (pin "1") (pinfunction "CS_1") (pintype "bidirectional"))
    )
    (net (code "165") (name "Net-(U$12-DI)") (class "Default")
      (node (ref "JP39") (pin "6") (pinfunction "6_6") (pintype "passive"))
      (node (ref "U$12") (pin "2") (pinfunction "DI_2") (pintype "bidirectional"))
    )
    (net (code "166") (name "Net-(U$12-DO)") (class "Default")
      (node (ref "JP39") (pin "2") (pinfunction "2_2") (pintype "passive"))
      (node (ref "U$12") (pin "6") (pinfunction "DO_6") (pintype "bidirectional"))
    )
    (net (code "167") (name "Net-(U$12-GND)") (class "Default")
      (node (ref "JP39") (pin "3") (pinfunction "3_3") (pintype "passive"))
      (node (ref "U$12") (pin "5") (pinfunction "GND_5") (pintype "bidirectional"))
    )
    (net (code "168") (name "Net-(U$12-SCK)") (class "Default")
      (node (ref "JP39") (pin "4") (pinfunction "4_4") (pintype "passive"))
      (node (ref "U$12") (pin "4") (pinfunction "SCK_4") (pintype "bidirectional"))
    )
    (net (code "169") (name "Net-(U$12-VCC)") (class "Default")
      (node (ref "JP39") (pin "5") (pinfunction "5_5") (pintype "passive"))
      (node (ref "U$12") (pin "3") (pinfunction "VCC_3") (pintype "bidirectional"))
    )
    (net (code "170") (name "Net-(U$17-A)") (class "Default")
      (node (ref "JP55") (pin "1") (pinfunction "1_1") (pintype "passive"))
      (node (ref "U$17") (pin "1") (pinfunction "A_1") (pintype "bidirectional"))
    )
    (net (code "171") (name "Net-(U$17-B)") (class "Default")
      (node (ref "JP53") (pin "1") (pinfunction "1_1") (pintype "passive"))
      (node (ref "U$17") (pin "3") (pinfunction "B_3") (pintype "bidirectional"))
    )
    (net (code "172") (name "Net-(U$17-W)") (class "Default")
      (node (ref "JP54") (pin "1") (pinfunction "1_1") (pintype "passive"))
      (node (ref "U$17") (pin "2") (pinfunction "W_2") (pintype "bidirectional"))
    )
    (net (code "173") (name "PWM_MO_1") (class "Default")
      (node (ref "IC2") (pin "1") (pinfunction "1-2EN_1") (pintype "input"))
      (node (ref "JP57") (pin "1") (pinfunction "1_1") (pintype "passive"))
    )
    (net (code "174") (name "PWM_MO_2") (class "Default")
      (node (ref "IC2") (pin "9") (pinfunction "3-4EN_9") (pintype "input"))
      (node (ref "JP58") (pin "2") (pinfunction "2_2") (pintype "passive"))
    )
    (net (code "175") (name "RS_DOG") (class "Default")
      (node (ref "JP1") (pin "2") (pinfunction "2_2") (pintype "passive"))
      (node (ref "LCD1") (pin "39") (pinfunction "RS_39") (pintype "bidirectional"))
      (node (ref "R9") (pin "1") (pinfunction "1_1") (pintype "passive"))
    )
    (net (code "176") (name "SI_DOG") (class "Default")
      (node (ref "JP1") (pin "4") (pinfunction "4_4") (pintype "passive"))
      (node (ref "LCD1") (pin "28") (pinfunction "D7_28") (pintype "bidirectional"))
      (node (ref "R12") (pin "1") (pinfunction "1_1") (pintype "passive"))
    )
    (net (code "177") (name "UEXT_3V3") (class "Default")
      (node (ref "JP20") (pin "1") (pinfunction "1_1") (pintype "passive"))
      (node (ref "JP63") (pin "1") (pinfunction "1_1") (pintype "passive"))
      (node (ref "SV2") (pin "1") (pinfunction "1_1") (pintype "passive"))
    )
    (net (code "178") (name "UEXT_GND") (class "Default")
      (node (ref "JP20") (pin "2") (pinfunction "2_2") (pintype "passive"))
      (node (ref "JP63") (pin "2") (pinfunction "2_2") (pintype "passive"))
      (node (ref "SV2") (pin "2") (pinfunction "2_2") (pintype "passive"))
    )
    (net (code "179") (name "UEXT_MISO") (class "Default")
      (node (ref "JP20") (pin "7") (pinfunction "7_7") (pintype "passive"))
      (node (ref "JP63") (pin "7") (pinfunction "7_7") (pintype "passive"))
      (node (ref "SV2") (pin "7") (pinfunction "7_7") (pintype "passive"))
    )
    (net (code "180") (name "UEXT_MOSI") (class "Default")
      (node (ref "JP20") (pin "8") (pinfunction "8_8") (pintype "passive"))
      (node (ref "JP63") (pin "8") (pinfunction "8_8") (pintype "passive"))
      (node (ref "SV2") (pin "8") (pinfunction "8_8") (pintype "passive"))
    )
    (net (code "181") (name "UEXT_RXD") (class "Default")
      (node (ref "JP20") (pin "4") (pinfunction "4_4") (pintype "passive"))
      (node (ref "JP63") (pin "4") (pinfunction "4_4") (pintype "passive"))
      (node (ref "SV2") (pin "4") (pinfunction "4_4") (pintype "passive"))
    )
    (net (code "182") (name "UEXT_SCK") (class "Default")
      (node (ref "JP20") (pin "9") (pinfunction "9_9") (pintype "passive"))
      (node (ref "JP63") (pin "9") (pinfunction "9_9") (pintype "passive"))
      (node (ref "SV2") (pin "9") (pinfunction "9_9") (pintype "passive"))
    )
    (net (code "183") (name "UEXT_SCL") (class "Default")
      (node (ref "JP20") (pin "5") (pinfunction "5_5") (pintype "passive"))
      (node (ref "JP63") (pin "5") (pinfunction "5_5") (pintype "passive"))
      (node (ref "SV2") (pin "5") (pinfunction "5_5") (pintype "passive"))
    )
    (net (code "184") (name "UEXT_SDA") (class "Default")
      (node (ref "JP20") (pin "6") (pinfunction "6_6") (pintype "passive"))
      (node (ref "JP63") (pin "6") (pinfunction "6_6") (pintype "passive"))
      (node (ref "SV2") (pin "6") (pinfunction "6_6") (pintype "passive"))
    )
    (net (code "185") (name "UEXT_SSEL") (class "Default")
      (node (ref "JP20") (pin "10") (pinfunction "10_10") (pintype "passive"))
      (node (ref "JP63") (pin "10") (pinfunction "10_10") (pintype "passive"))
      (node (ref "SV2") (pin "10") (pinfunction "10_10") (pintype "passive"))
    )
    (net (code "186") (name "UEXT_TXD") (class "Default")
      (node (ref "JP20") (pin "3") (pinfunction "3_3") (pintype "passive"))
      (node (ref "JP63") (pin "3") (pinfunction "3_3") (pintype "passive"))
      (node (ref "SV2") (pin "3") (pinfunction "3_3") (pintype "passive"))
    )
    (net (code "187") (name "V3V_DOG") (class "Default")
      (node (ref "C3") (pin "1") (pinfunction "1_1") (pintype "passive"))
      (node (ref "JP1") (pin "5") (pinfunction "5_5") (pintype "passive"))
      (node (ref "LCD1") (pin "25") (pinfunction "VIN_25") (pintype "bidirectional"))
      (node (ref "LCD1") (pin "26") (pinfunction "VDD_26") (pintype "bidirectional"))
      (node (ref "R10") (pin "2") (pinfunction "2_2") (pintype "passive"))
      (node (ref "R7") (pin "2") (pinfunction "2_2") (pintype "passive"))
      (node (ref "R8") (pin "2") (pinfunction "2_2") (pintype "passive"))
    )
    (net (code "188") (name "unconnected-(3V3-PadSHDN_N)") (class "Default")
      (node (ref "3V3") (pin "SHDN_N") (pinfunction "SHDN_N_SHDN_N") (pintype "bidirectional"))
    )
    (net (code "189") (name "unconnected-(5V-PadSHDN_N)") (class "Default")
      (node (ref "5V") (pin "SHDN_N") (pinfunction "SHDN_N_SHDN_N") (pintype "bidirectional"))
    )
    (net (code "190") (name "unconnected-(JP4-Pad3)") (class "Default")
      (node (ref "JP4") (pin "3") (pinfunction "3_3") (pintype "passive"))
    )
    (net (code "191") (name "unconnected-(JP59-Pad1)") (class "Default")
      (node (ref "JP59") (pin "1") (pinfunction "1_1") (pintype "passive"))
    )
    (net (code "192") (name "unconnected-(JP60-Pad1)") (class "Default")
      (node (ref "JP60") (pin "1") (pinfunction "1_1") (pintype "passive"))
    )
    (net (code "193") (name "unconnected-(JP61-Pad1)") (class "Default")
      (node (ref "JP61") (pin "1") (pinfunction "1_1") (pintype "passive"))
    )
    (net (code "194") (name "unconnected-(JP62-Pad1)") (class "Default")
      (node (ref "JP62") (pin "1") (pinfunction "1_1") (pintype "passive"))
    )
    (net (code "195") (name "unconnected-(U$1-EXT_3V3_VL-Pad3V3_EXT_VL)") (class "Default")
      (node (ref "U$1") (pin "3V3_EXT_VL") (pinfunction "EXT_3V3_VL_3V3_EXT_VL") (pintype "bidirectional"))
    )
    (net (code "196") (name "unconnected-(U$1-EXT_VBAT_VL-PadVBAT_EXT_VL)") (class "Default")
      (node (ref "U$1") (pin "VBAT_EXT_VL") (pinfunction "EXT_VBAT_VL_VBAT_EXT_VL") (pintype "bidirectional"))
    )
    (net (code "197") (name "unconnected-(U$1-GND_3_R_FO-PadGND_3_R_F0)") (class "Default")
      (node (ref "U$1") (pin "GND_3_R_F0") (pinfunction "GND_3_R_FO_GND_3_R_F0") (pintype "bidirectional"))
    )
    (net (code "198") (name "unconnected-(U$1-Pad3V_F0)") (class "Default")
      (node (ref "U$1") (pin "3V_F0") (pinfunction "3V_F0_3V_F0") (pintype "bidirectional"))
    )
    (net (code "199") (name "unconnected-(U$1-Pad5V_F0)") (class "Default")
      (node (ref "U$1") (pin "5V_F0") (pinfunction "5V_F0_5V_F0") (pintype "bidirectional"))
    )
    (net (code "200") (name "unconnected-(U$1-PadBOOT0_F0)") (class "Default")
      (node (ref "U$1") (pin "BOOT0_F0") (pinfunction "BOOT0_F0_BOOT0_F0") (pintype "bidirectional"))
    )
    (net (code "201") (name "unconnected-(U$1-PadBOOT0_VL)") (class "Default")
      (node (ref "U$1") (pin "BOOT0_VL") (pinfunction "BOOT0_VL_BOOT0_VL") (pintype "bidirectional"))
    )
    (net (code "202") (name "unconnected-(U$1-PadEXT_5V_VL)") (class "Default")
      (node (ref "U$1") (pin "EXT_5V_VL") (pinfunction "EXT_5V_VL_EXT_5V_VL") (pintype "bidirectional"))
    )
    (net (code "203") (name "unconnected-(U$1-PadGND_0_L_F0)") (class "Default")
      (node (ref "U$1") (pin "GND_0_L_F0") (pinfunction "GND_0_L_F0_GND_0_L_F0") (pintype "bidirectional"))
    )
    (net (code "204") (name "unconnected-(U$1-PadGND_0_L_VL)") (class "Default")
      (node (ref "U$1") (pin "GND_0_L_VL") (pinfunction "GND_0_L_VL_GND_0_L_VL") (pintype "bidirectional"))
    )
    (net (code "205") (name "unconnected-(U$1-PadGND_1_L_F0)") (class "Default")
      (node (ref "U$1") (pin "GND_1_L_F0") (pinfunction "GND_1_L_F0_GND_1_L_F0") (pintype "bidirectional"))
    )
    (net (code "206") (name "unconnected-(U$1-PadGND_2_L_F0)") (class "Default")
      (node (ref "U$1") (pin "GND_2_L_F0") (pinfunction "GND_2_L_F0_GND_2_L_F0") (pintype "bidirectional"))
    )
    (net (code "207") (name "unconnected-(U$1-PadGND_2_R_VL)") (class "Default")
      (node (ref "U$1") (pin "GND_2_R_VL") (pinfunction "GND_2_R_VL_GND_2_R_VL") (pintype "bidirectional"))
    )
    (net (code "208") (name "unconnected-(U$1-PadGND_3_R_VL)") (class "Default")
      (node (ref "U$1") (pin "GND_3_R_VL") (pinfunction "GND_3_R_VL_GND_3_R_VL") (pintype "bidirectional"))
    )
    (net (code "209") (name "unconnected-(U$1-PadGND_4_R_F0)") (class "Default")
      (node (ref "U$1") (pin "GND_4_R_F0") (pinfunction "GND_4_R_F0_GND_4_R_F0") (pintype "bidirectional"))
    )
    (net (code "210") (name "unconnected-(U$1-PadNC_L_VL)") (class "Default")
      (node (ref "U$1") (pin "NC_L_VL") (pinfunction "NC_L_VL_NC_L_VL") (pintype "bidirectional"))
    )
    (net (code "211") (name "unconnected-(U$1-PadNC_R_VL)") (class "Default")
      (node (ref "U$1") (pin "NC_R_VL") (pinfunction "NC_R_VL_NC_R_VL") (pintype "bidirectional"))
    )
    (net (code "212") (name "unconnected-(U$1-PadNRST_F0)") (class "Default")
      (node (ref "U$1") (pin "NRST_F0") (pinfunction "NRST_F0_NRST_F0") (pintype "bidirectional"))
    )
    (net (code "213") (name "unconnected-(U$1-PadPA0_F0)") (class "Default")
      (node (ref "U$1") (pin "PA0_F0") (pinfunction "PA0_F0_PA0_F0") (pintype "bidirectional"))
    )
    (net (code "214") (name "unconnected-(U$1-PadPA0_VL)") (class "Default")
      (node (ref "U$1") (pin "PA0_VL") (pinfunction "PA0_VL_PA0_VL") (pintype "bidirectional"))
    )
    (net (code "215") (name "unconnected-(U$1-PadPA1_F0)") (class "Default")
      (node (ref "U$1") (pin "PA1_F0") (pinfunction "PA1_F0_PA1_F0") (pintype "output"))
    )
    (net (code "216") (name "unconnected-(U$1-PadPA1_VL)") (class "Default")
      (node (ref "U$1") (pin "PA1_VL") (pinfunction "PA1_VL_PA1_VL") (pintype "bidirectional"))
    )
    (net (code "217") (name "unconnected-(U$1-PadPA2_F0)") (class "Default")
      (node (ref "U$1") (pin "PA2_F0") (pinfunction "PA2_F0_PA2_F0") (pintype "bidirectional"))
    )
    (net (code "218") (name "unconnected-(U$1-PadPA2_VL)") (class "Default")
      (node (ref "U$1") (pin "PA2_VL") (pinfunction "PA2_VL_PA2_VL") (pintype "bidirectional"))
    )
    (net (code "219") (name "unconnected-(U$1-PadPA3_F0)") (class "Default")
      (node (ref "U$1") (pin "PA3_F0") (pinfunction "PA3_F0_PA3_F0") (pintype "bidirectional"))
    )
    (net (code "220") (name "unconnected-(U$1-PadPA3_VL)") (class "Default")
      (node (ref "U$1") (pin "PA3_VL") (pinfunction "PA3_VL_PA3_VL") (pintype "bidirectional"))
    )
    (net (code "221") (name "unconnected-(U$1-PadPA4_F0)") (class "Default")
      (node (ref "U$1") (pin "PA4_F0") (pinfunction "PA4_F0_PA4_F0") (pintype "bidirectional"))
    )
    (net (code "222") (name "unconnected-(U$1-PadPA4_VL)") (class "Default")
      (node (ref "U$1") (pin "PA4_VL") (pinfunction "PA4_VL_PA4_VL") (pintype "bidirectional"))
    )
    (net (code "223") (name "unconnected-(U$1-PadPA5_F0)") (class "Default")
      (node (ref "U$1") (pin "PA5_F0") (pinfunction "PA5_F0_PA5_F0") (pintype "bidirectional"))
    )
    (net (code "224") (name "unconnected-(U$1-PadPA5_VL)") (class "Default")
      (node (ref "U$1") (pin "PA5_VL") (pinfunction "PA5_VL_PA5_VL") (pintype "bidirectional"))
    )
    (net (code "225") (name "unconnected-(U$1-PadPA6_F0)") (class "Default")
      (node (ref "U$1") (pin "PA6_F0") (pinfunction "PA6_F0_PA6_F0") (pintype "bidirectional"))
    )
    (net (code "226") (name "unconnected-(U$1-PadPA6_VL)") (class "Default")
      (node (ref "U$1") (pin "PA6_VL") (pinfunction "PA6_VL_PA6_VL") (pintype "bidirectional"))
    )
    (net (code "227") (name "unconnected-(U$1-PadPA7_F0)") (class "Default")
      (node (ref "U$1") (pin "PA7_F0") (pinfunction "PA7_F0_PA7_F0") (pintype "bidirectional"))
    )
    (net (code "228") (name "unconnected-(U$1-PadPA7_VL)") (class "Default")
      (node (ref "U$1") (pin "PA7_VL") (pinfunction "PA7_VL_PA7_VL") (pintype "bidirectional"))
    )
    (net (code "229") (name "unconnected-(U$1-PadPA8_F0)") (class "Default")
      (node (ref "U$1") (pin "PA8_F0") (pinfunction "PA8_F0_PA8_F0") (pintype "bidirectional"))
    )
    (net (code "230") (name "unconnected-(U$1-PadPA8_VL)") (class "Default")
      (node (ref "U$1") (pin "PA8_VL") (pinfunction "PA8_VL_PA8_VL") (pintype "bidirectional"))
    )
    (net (code "231") (name "unconnected-(U$1-PadPA9_F0)") (class "Default")
      (node (ref "U$1") (pin "PA9_F0") (pinfunction "PA9_F0_PA9_F0") (pintype "bidirectional"))
    )
    (net (code "232") (name "unconnected-(U$1-PadPA9_VL)") (class "Default")
      (node (ref "U$1") (pin "PA9_VL") (pinfunction "PA9_VL_PA9_VL") (pintype "bidirectional"))
    )
    (net (code "233") (name "unconnected-(U$1-PadPA10_F0)") (class "Default")
      (node (ref "U$1") (pin "PA10_F0") (pinfunction "PA10_F0_PA10_F0") (pintype "bidirectional"))
    )
    (net (code "234") (name "unconnected-(U$1-PadPA10_VL)") (class "Default")
      (node (ref "U$1") (pin "PA10_VL") (pinfunction "PA10_VL_PA10_VL") (pintype "bidirectional"))
    )
    (net (code "235") (name "unconnected-(U$1-PadPA11_F0)") (class "Default")
      (node (ref "U$1") (pin "PA11_F0") (pinfunction "PA11_F0_PA11_F0") (pintype "bidirectional"))
    )
    (net (code "236") (name "unconnected-(U$1-PadPA11_VL)") (class "Default")
      (node (ref "U$1") (pin "PA11_VL") (pinfunction "PA11_VL_PA11_VL") (pintype "bidirectional"))
    )
    (net (code "237") (name "unconnected-(U$1-PadPA12_F0)") (class "Default")
      (node (ref "U$1") (pin "PA12_F0") (pinfunction "PA12_F0_PA12_F0") (pintype "bidirectional"))
    )
    (net (code "238") (name "unconnected-(U$1-PadPA12_VL)") (class "Default")
      (node (ref "U$1") (pin "PA12_VL") (pinfunction "PA12_VL_PA12_VL") (pintype "bidirectional"))
    )
    (net (code "239") (name "unconnected-(U$1-PadPA13_F0)") (class "Default")
      (node (ref "U$1") (pin "PA13_F0") (pinfunction "PA13_F0_PA13_F0") (pintype "bidirectional"))
    )
    (net (code "240") (name "unconnected-(U$1-PadPA13_VL)") (class "Default")
      (node (ref "U$1") (pin "PA13_VL") (pinfunction "PA13_VL_PA13_VL") (pintype "bidirectional"))
    )
    (net (code "241") (name "unconnected-(U$1-PadPA14_F0)") (class "Default")
      (node (ref "U$1") (pin "PA14_F0") (pinfunction "PA14_F0_PA14_F0") (pintype "bidirectional"))
    )
    (net (code "242") (name "unconnected-(U$1-PadPA14_VL)") (class "Default")
      (node (ref "U$1") (pin "PA14_VL") (pinfunction "PA14_VL_PA14_VL") (pintype "bidirectional"))
    )
    (net (code "243") (name "unconnected-(U$1-PadPA15_F0)") (class "Default")
      (node (ref "U$1") (pin "PA15_F0") (pinfunction "PA15_F0_PA15_F0") (pintype "bidirectional"))
    )
    (net (code "244") (name "unconnected-(U$1-PadPA15_VL)") (class "Default")
      (node (ref "U$1") (pin "PA15_VL") (pinfunction "PA15_VL_PA15_VL") (pintype "bidirectional"))
    )
    (net (code "245") (name "unconnected-(U$1-PadPB0_F0)") (class "Default")
      (node (ref "U$1") (pin "PB0_F0") (pinfunction "PB0_F0_PB0_F0") (pintype "bidirectional"))
    )
    (net (code "246") (name "unconnected-(U$1-PadPB0_VL)") (class "Default")
      (node (ref "U$1") (pin "PB0_VL") (pinfunction "PB0_VL_PB0_VL") (pintype "bidirectional"))
    )
    (net (code "247") (name "unconnected-(U$1-PadPB1_F0)") (class "Default")
      (node (ref "U$1") (pin "PB1_F0") (pinfunction "PB1_F0_PB1_F0") (pintype "bidirectional"))
    )
    (net (code "248") (name "unconnected-(U$1-PadPB1_VL)") (class "Default")
      (node (ref "U$1") (pin "PB1_VL") (pinfunction "PB1_VL_PB1_VL") (pintype "bidirectional"))
    )
    (net (code "249") (name "unconnected-(U$1-PadPB2_F0)") (class "Default")
      (node (ref "U$1") (pin "PB2_F0") (pinfunction "PB2_F0_PB2_F0") (pintype "bidirectional"))
    )
    (net (code "250") (name "unconnected-(U$1-PadPB2_VL)") (class "Default")
      (node (ref "U$1") (pin "PB2_VL") (pinfunction "PB2_VL_PB2_VL") (pintype "bidirectional"))
    )
    (net (code "251") (name "unconnected-(U$1-PadPB3_F0)") (class "Default")
      (node (ref "U$1") (pin "PB3_F0") (pinfunction "PB3_F0_PB3_F0") (pintype "bidirectional"))
    )
    (net (code "252") (name "unconnected-(U$1-PadPB3_VL)") (class "Default")
      (node (ref "U$1") (pin "PB3_VL") (pinfunction "PB3_VL_PB3_VL") (pintype "bidirectional"))
    )
    (net (code "253") (name "unconnected-(U$1-PadPB4_F0)") (class "Default")
      (node (ref "U$1") (pin "PB4_F0") (pinfunction "PB4_F0_PB4_F0") (pintype "bidirectional"))
    )
    (net (code "254") (name "unconnected-(U$1-PadPB4_VL)") (class "Default")
      (node (ref "U$1") (pin "PB4_VL") (pinfunction "PB4_VL_PB4_VL") (pintype "bidirectional"))
    )
    (net (code "255") (name "unconnected-(U$1-PadPB5_F0)") (class "Default")
      (node (ref "U$1") (pin "PB5_F0") (pinfunction "PB5_F0_PB5_F0") (pintype "bidirectional"))
    )
    (net (code "256") (name "unconnected-(U$1-PadPB5_VL)") (class "Default")
      (node (ref "U$1") (pin "PB5_VL") (pinfunction "PB5_VL_PB5_VL") (pintype "bidirectional"))
    )
    (net (code "257") (name "unconnected-(U$1-PadPB6_F0)") (class "Default")
      (node (ref "U$1") (pin "PB6_F0") (pinfunction "PB6_F0_PB6_F0") (pintype "bidirectional"))
    )
    (net (code "258") (name "unconnected-(U$1-PadPB6_VL)") (class "Default")
      (node (ref "U$1") (pin "PB6_VL") (pinfunction "PB6_VL_PB6_VL") (pintype "bidirectional"))
    )
    (net (code "259") (name "unconnected-(U$1-PadPB7_F0)") (class "Default")
      (node (ref "U$1") (pin "PB7_F0") (pinfunction "PB7_F0_PB7_F0") (pintype "bidirectional"))
    )
    (net (code "260") (name "unconnected-(U$1-PadPB7_VL)") (class "Default")
      (node (ref "U$1") (pin "PB7_VL") (pinfunction "PB7_VL_PB7_VL") (pintype "bidirectional"))
    )
    (net (code "261") (name "unconnected-(U$1-PadPB8_F0)") (class "Default")
      (node (ref "U$1") (pin "PB8_F0") (pinfunction "PB8_F0_PB8_F0") (pintype "bidirectional"))
    )
    (net (code "262") (name "unconnected-(U$1-PadPB8_VL)") (class "Default")
      (node (ref "U$1") (pin "PB8_VL") (pinfunction "PB8_VL_PB8_VL") (pintype "bidirectional"))
    )
    (net (code "263") (name "unconnected-(U$1-PadPB9_F0)") (class "Default")
      (node (ref "U$1") (pin "PB9_F0") (pinfunction "PB9_F0_PB9_F0") (pintype "bidirectional"))
    )
    (net (code "264") (name "unconnected-(U$1-PadPB9_VL)") (class "Default")
      (node (ref "U$1") (pin "PB9_VL") (pinfunction "PB9_VL_PB9_VL") (pintype "bidirectional"))
    )
    (net (code "265") (name "unconnected-(U$1-PadPB10_F0)") (class "Default")
      (node (ref "U$1") (pin "PB10_F0") (pinfunction "PB10_F0_PB10_F0") (pintype "bidirectional"))
    )
    (net (code "266") (name "unconnected-(U$1-PadPB10_VL)") (class "Default")
      (node (ref "U$1") (pin "PB10_VL") (pinfunction "PB10_VL_PB10_VL") (pintype "bidirectional"))
    )
    (net (code "267") (name "unconnected-(U$1-PadPB11_F0)") (class "Default")
      (node (ref "U$1") (pin "PB11_F0") (pinfunction "PB11_F0_PB11_F0") (pintype "bidirectional"))
    )
    (net (code "268") (name "unconnected-(U$1-PadPB11_VL)") (class "Default")
      (node (ref "U$1") (pin "PB11_VL") (pinfunction "PB11_VL_PB11_VL") (pintype "bidirectional"))
    )
    (net (code "269") (name "unconnected-(U$1-PadPB12_F0)") (class "Default")
      (node (ref "U$1") (pin "PB12_F0") (pinfunction "PB12_F0_PB12_F0") (pintype "bidirectional"))
    )
    (net (code "270") (name "unconnected-(U$1-PadPB12_VL)") (class "Default")
      (node (ref "U$1") (pin "PB12_VL") (pinfunction "PB12_VL_PB12_VL") (pintype "bidirectional"))
    )
    (net (code "271") (name "unconnected-(U$1-PadPB13_F0)") (class "Default")
      (node (ref "U$1") (pin "PB13_F0") (pinfunction "PB13_F0_PB13_F0") (pintype "bidirectional"))
    )
    (net (code "272") (name "unconnected-(U$1-PadPB13_VL)") (class "Default")
      (node (ref "U$1") (pin "PB13_VL") (pinfunction "PB13_VL_PB13_VL") (pintype "bidirectional"))
    )
    (net (code "273") (name "unconnected-(U$1-PadPB14_F0)") (class "Default")
      (node (ref "U$1") (pin "PB14_F0") (pinfunction "PB14_F0_PB14_F0") (pintype "bidirectional"))
    )
    (net (code "274") (name "unconnected-(U$1-PadPB14_VL)") (class "Default")
      (node (ref "U$1") (pin "PB14_VL") (pinfunction "PB14_VL_PB14_VL") (pintype "bidirectional"))
    )
    (net (code "275") (name "unconnected-(U$1-PadPB15_F0)") (class "Default")
      (node (ref "U$1") (pin "PB15_F0") (pinfunction "PB15_F0_PB15_F0") (pintype "bidirectional"))
    )
    (net (code "276") (name "unconnected-(U$1-PadPB15_VL)") (class "Default")
      (node (ref "U$1") (pin "PB15_VL") (pinfunction "PB15_VL_PB15_VL") (pintype "bidirectional"))
    )
    (net (code "277") (name "unconnected-(U$1-PadPC0_F0)") (class "Default")
      (node (ref "U$1") (pin "PC0_F0") (pinfunction "PC0_F0_PC0_F0") (pintype "bidirectional"))
    )
    (net (code "278") (name "unconnected-(U$1-PadPC0_VL)") (class "Default")
      (node (ref "U$1") (pin "PC0_VL") (pinfunction "PC0_VL_PC0_VL") (pintype "bidirectional"))
    )
    (net (code "279") (name "unconnected-(U$1-PadPC1_F0)") (class "Default")
      (node (ref "U$1") (pin "PC1_F0") (pinfunction "PC1_F0_PC1_F0") (pintype "bidirectional"))
    )
    (net (code "280") (name "unconnected-(U$1-PadPC1_VL)") (class "Default")
      (node (ref "U$1") (pin "PC1_VL") (pinfunction "PC1_VL_PC1_VL") (pintype "bidirectional"))
    )
    (net (code "281") (name "unconnected-(U$1-PadPC2_F0)") (class "Default")
      (node (ref "U$1") (pin "PC2_F0") (pinfunction "PC2_F0_PC2_F0") (pintype "bidirectional"))
    )
    (net (code "282") (name "unconnected-(U$1-PadPC2_VL)") (class "Default")
      (node (ref "U$1") (pin "PC2_VL") (pinfunction "PC2_VL_PC2_VL") (pintype "bidirectional"))
    )
    (net (code "283") (name "unconnected-(U$1-PadPC3_F0)") (class "Default")
      (node (ref "U$1") (pin "PC3_F0") (pinfunction "PC3_F0_PC3_F0") (pintype "bidirectional"))
    )
    (net (code "284") (name "unconnected-(U$1-PadPC3_VL)") (class "Default")
      (node (ref "U$1") (pin "PC3_VL") (pinfunction "PC3_VL_PC3_VL") (pintype "bidirectional"))
    )
    (net (code "285") (name "unconnected-(U$1-PadPC4_F0)") (class "Default")
      (node (ref "U$1") (pin "PC4_F0") (pinfunction "PC4_F0_PC4_F0") (pintype "bidirectional"))
    )
    (net (code "286") (name "unconnected-(U$1-PadPC4_VL)") (class "Default")
      (node (ref "U$1") (pin "PC4_VL") (pinfunction "PC4_VL_PC4_VL") (pintype "bidirectional"))
    )
    (net (code "287") (name "unconnected-(U$1-PadPC5_F0)") (class "Default")
      (node (ref "U$1") (pin "PC5_F0") (pinfunction "PC5_F0_PC5_F0") (pintype "bidirectional"))
    )
    (net (code "288") (name "unconnected-(U$1-PadPC5_VL)") (class "Default")
      (node (ref "U$1") (pin "PC5_VL") (pinfunction "PC5_VL_PC5_VL") (pintype "bidirectional"))
    )
    (net (code "289") (name "unconnected-(U$1-PadPC6_F0)") (class "Default")
      (node (ref "U$1") (pin "PC6_F0") (pinfunction "PC6_F0_PC6_F0") (pintype "bidirectional"))
    )
    (net (code "290") (name "unconnected-(U$1-PadPC6_VL)") (class "Default")
      (node (ref "U$1") (pin "PC6_VL") (pinfunction "PC6_VL_PC6_VL") (pintype "bidirectional"))
    )
    (net (code "291") (name "unconnected-(U$1-PadPC7_F0)") (class "Default")
      (node (ref "U$1") (pin "PC7_F0") (pinfunction "PC7_F0_PC7_F0") (pintype "bidirectional"))
    )
    (net (code "292") (name "unconnected-(U$1-PadPC7_VL)") (class "Default")
      (node (ref "U$1") (pin "PC7_VL") (pinfunction "PC7_VL_PC7_VL") (pintype "bidirectional"))
    )
    (net (code "293") (name "unconnected-(U$1-PadPC8_F0)") (class "Default")
      (node (ref "U$1") (pin "PC8_F0") (pinfunction "PC8_F0_PC8_F0") (pintype "bidirectional"))
    )
    (net (code "294") (name "unconnected-(U$1-PadPC8_VL)") (class "Default")
      (node (ref "U$1") (pin "PC8_VL") (pinfunction "PC8_VL_PC8_VL") (pintype "bidirectional"))
    )
    (net (code "295") (name "unconnected-(U$1-PadPC9_F0)") (class "Default")
      (node (ref "U$1") (pin "PC9_F0") (pinfunction "PC9_F0_PC9_F0") (pintype "bidirectional"))
    )
    (net (code "296") (name "unconnected-(U$1-PadPC9_VL)") (class "Default")
      (node (ref "U$1") (pin "PC9_VL") (pinfunction "PC9_VL_PC9_VL") (pintype "bidirectional"))
    )
    (net (code "297") (name "unconnected-(U$1-PadPC10_F0)") (class "Default")
      (node (ref "U$1") (pin "PC10_F0") (pinfunction "PC10_F0_PC10_F0") (pintype "bidirectional"))
    )
    (net (code "298") (name "unconnected-(U$1-PadPC10_VL)") (class "Default")
      (node (ref "U$1") (pin "PC10_VL") (pinfunction "PC10_VL_PC10_VL") (pintype "bidirectional"))
    )
    (net (code "299") (name "unconnected-(U$1-PadPC11_F0)") (class "Default")
      (node (ref "U$1") (pin "PC11_F0") (pinfunction "PC11_F0_PC11_F0") (pintype "bidirectional"))
    )
    (net (code "300") (name "unconnected-(U$1-PadPC11_VL)") (class "Default")
      (node (ref "U$1") (pin "PC11_VL") (pinfunction "PC11_VL_PC11_VL") (pintype "bidirectional"))
    )
    (net (code "301") (name "unconnected-(U$1-PadPC12_F0)") (class "Default")
      (node (ref "U$1") (pin "PC12_F0") (pinfunction "PC12_F0_PC12_F0") (pintype "bidirectional"))
    )
    (net (code "302") (name "unconnected-(U$1-PadPC12_VL)") (class "Default")
      (node (ref "U$1") (pin "PC12_VL") (pinfunction "PC12_VL_PC12_VL") (pintype "bidirectional"))
    )
    (net (code "303") (name "unconnected-(U$1-PadPC13_F0)") (class "Default")
      (node (ref "U$1") (pin "PC13_F0") (pinfunction "PC13_F0_PC13_F0") (pintype "bidirectional"))
    )
    (net (code "304") (name "unconnected-(U$1-PadPC13_VL)") (class "Default")
      (node (ref "U$1") (pin "PC13_VL") (pinfunction "PC13_VL_PC13_VL") (pintype "bidirectional"))
    )
    (net (code "305") (name "unconnected-(U$1-PadPC14_F0)") (class "Default")
      (node (ref "U$1") (pin "PC14_F0") (pinfunction "PC14_F0_PC14_F0") (pintype "bidirectional"))
    )
    (net (code "306") (name "unconnected-(U$1-PadPC14_VL)") (class "Default")
      (node (ref "U$1") (pin "PC14_VL") (pinfunction "PC14_VL_PC14_VL") (pintype "bidirectional"))
    )
    (net (code "307") (name "unconnected-(U$1-PadPC15_F0)") (class "Default")
      (node (ref "U$1") (pin "PC15_F0") (pinfunction "PC15_F0_PC15_F0") (pintype "bidirectional"))
    )
    (net (code "308") (name "unconnected-(U$1-PadPC15_VL)") (class "Default")
      (node (ref "U$1") (pin "PC15_VL") (pinfunction "PC15_VL_PC15_VL") (pintype "bidirectional"))
    )
    (net (code "309") (name "unconnected-(U$1-PadPD0_VL)") (class "Default")
      (node (ref "U$1") (pin "PD0_VL") (pinfunction "PD0_VL_PD0_VL") (pintype "bidirectional"))
    )
    (net (code "310") (name "unconnected-(U$1-PadPD1_VL)") (class "Default")
      (node (ref "U$1") (pin "PD1_VL") (pinfunction "PD1_VL_PD1_VL") (pintype "bidirectional"))
    )
    (net (code "311") (name "unconnected-(U$1-PadPD2_F0)") (class "Default")
      (node (ref "U$1") (pin "PD2_F0") (pinfunction "PD2_F0_PD2_F0") (pintype "bidirectional"))
    )
    (net (code "312") (name "unconnected-(U$1-PadPD2_VL)") (class "Default")
      (node (ref "U$1") (pin "PD2_VL") (pinfunction "PD2_VL_PD2_VL") (pintype "bidirectional"))
    )
    (net (code "313") (name "unconnected-(U$1-PadPF0_F0)") (class "Default")
      (node (ref "U$1") (pin "PF0_F0") (pinfunction "PF0_F0_PF0_F0") (pintype "bidirectional"))
    )
    (net (code "314") (name "unconnected-(U$1-PadPF1_F0)") (class "Default")
      (node (ref "U$1") (pin "PF1_F0") (pinfunction "PF1_F0_PF1_F0") (pintype "bidirectional"))
    )
    (net (code "315") (name "unconnected-(U$1-PadPF4_F0)") (class "Default")
      (node (ref "U$1") (pin "PF4_F0") (pinfunction "PF4_F0_PF4_F0") (pintype "bidirectional"))
    )
    (net (code "316") (name "unconnected-(U$1-PadPF5_F0)") (class "Default")
      (node (ref "U$1") (pin "PF5_F0") (pinfunction "PF5_F0_PF5_F0") (pintype "bidirectional"))
    )
    (net (code "317") (name "unconnected-(U$1-PadPF6_F0)") (class "Default")
      (node (ref "U$1") (pin "PF6_F0") (pinfunction "PF6_F0_PF6_F0") (pintype "bidirectional"))
    )
    (net (code "318") (name "unconnected-(U$1-PadPF7_F0)") (class "Default")
      (node (ref "U$1") (pin "PF7_F0") (pinfunction "PF7_F0_PF7_F0") (pintype "bidirectional"))
    )
    (net (code "319") (name "unconnected-(U$1-PadVBAT_F0)") (class "Default")
      (node (ref "U$1") (pin "VBAT_F0") (pinfunction "VBAT_F0_VBAT_F0") (pintype "bidirectional"))
    )
    (net (code "320") (name "unconnected-(U$1-PadVDD_F0)") (class "Default")
      (node (ref "U$1") (pin "VDD_F0") (pinfunction "VDD_F0_VDD_F0") (pintype "bidirectional"))
    )
    (net (code "321") (name "unconnected-(U$1-RESET#_VL-PadRESET_VL)") (class "Default")
      (node (ref "U$1") (pin "RESET_VL") (pinfunction "RESET#_VL_RESET_VL") (pintype "bidirectional"))
    )
    (net (code "322") (name "unconnected-(X1-Pad3)") (class "Default")
      (node (ref "X1") (pin "3") (pinfunction "3_3") (pintype "passive"))
    )
    (net (code "323") (name "unconnected-(X2A-KL-Pad1)") (class "Default")
      (node (ref "X2") (pin "1") (pinfunction "KL_1") (pintype "passive"))
    )
    (net (code "324") (name "unconnected-(X2B-KL-Pad2)") (class "Default")
      (node (ref "X2") (pin "2") (pinfunction "KL_2") (pintype "passive"))
    )
    (net (code "325") (name "unconnected-(X2C-KL-Pad3)") (class "Default")
      (node (ref "X2") (pin "3") (pinfunction "KL_3") (pintype "passive"))
    )
    (net (code "326") (name "unconnected-(X2D-KL-Pad4)") (class "Default")
      (node (ref "X2") (pin "4") (pinfunction "KL_4") (pintype "passive"))
    )
  )
)
